# MiniPrinterController.net
KiCad netlist of a schematic drawn in EAGLE
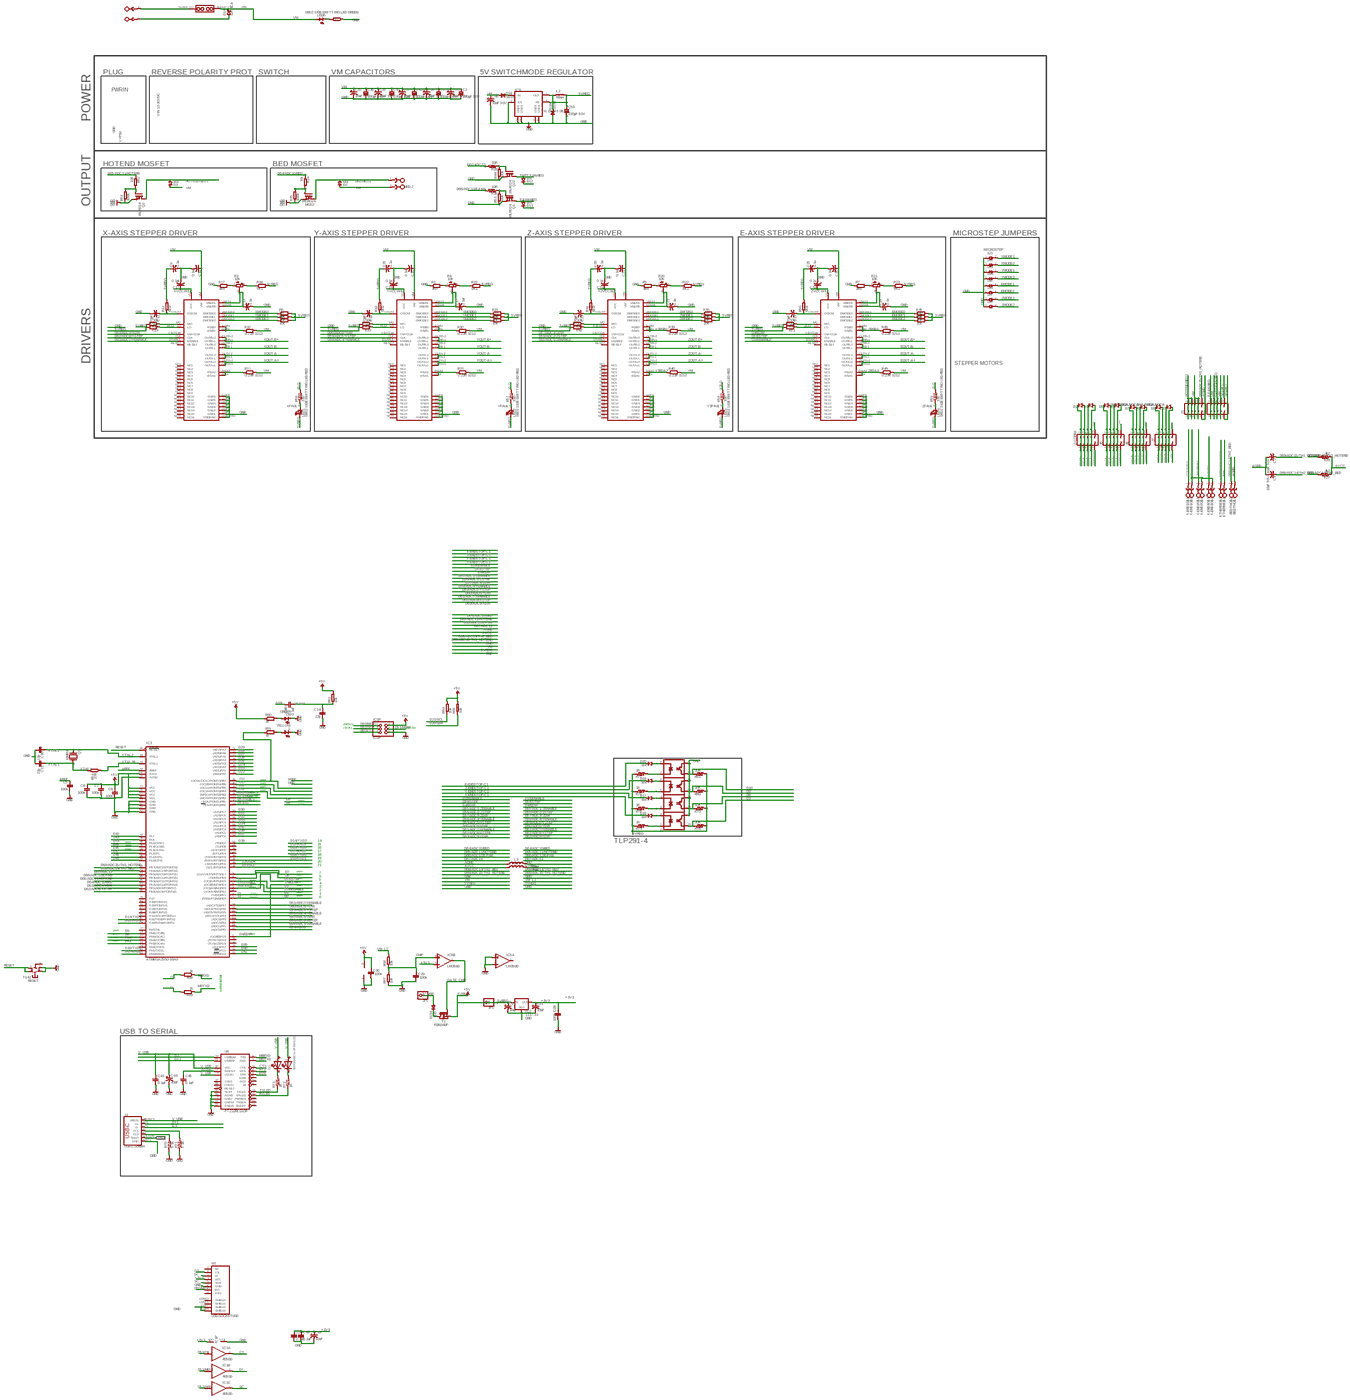
[diagram p0: schematic, sheet 1, overview]
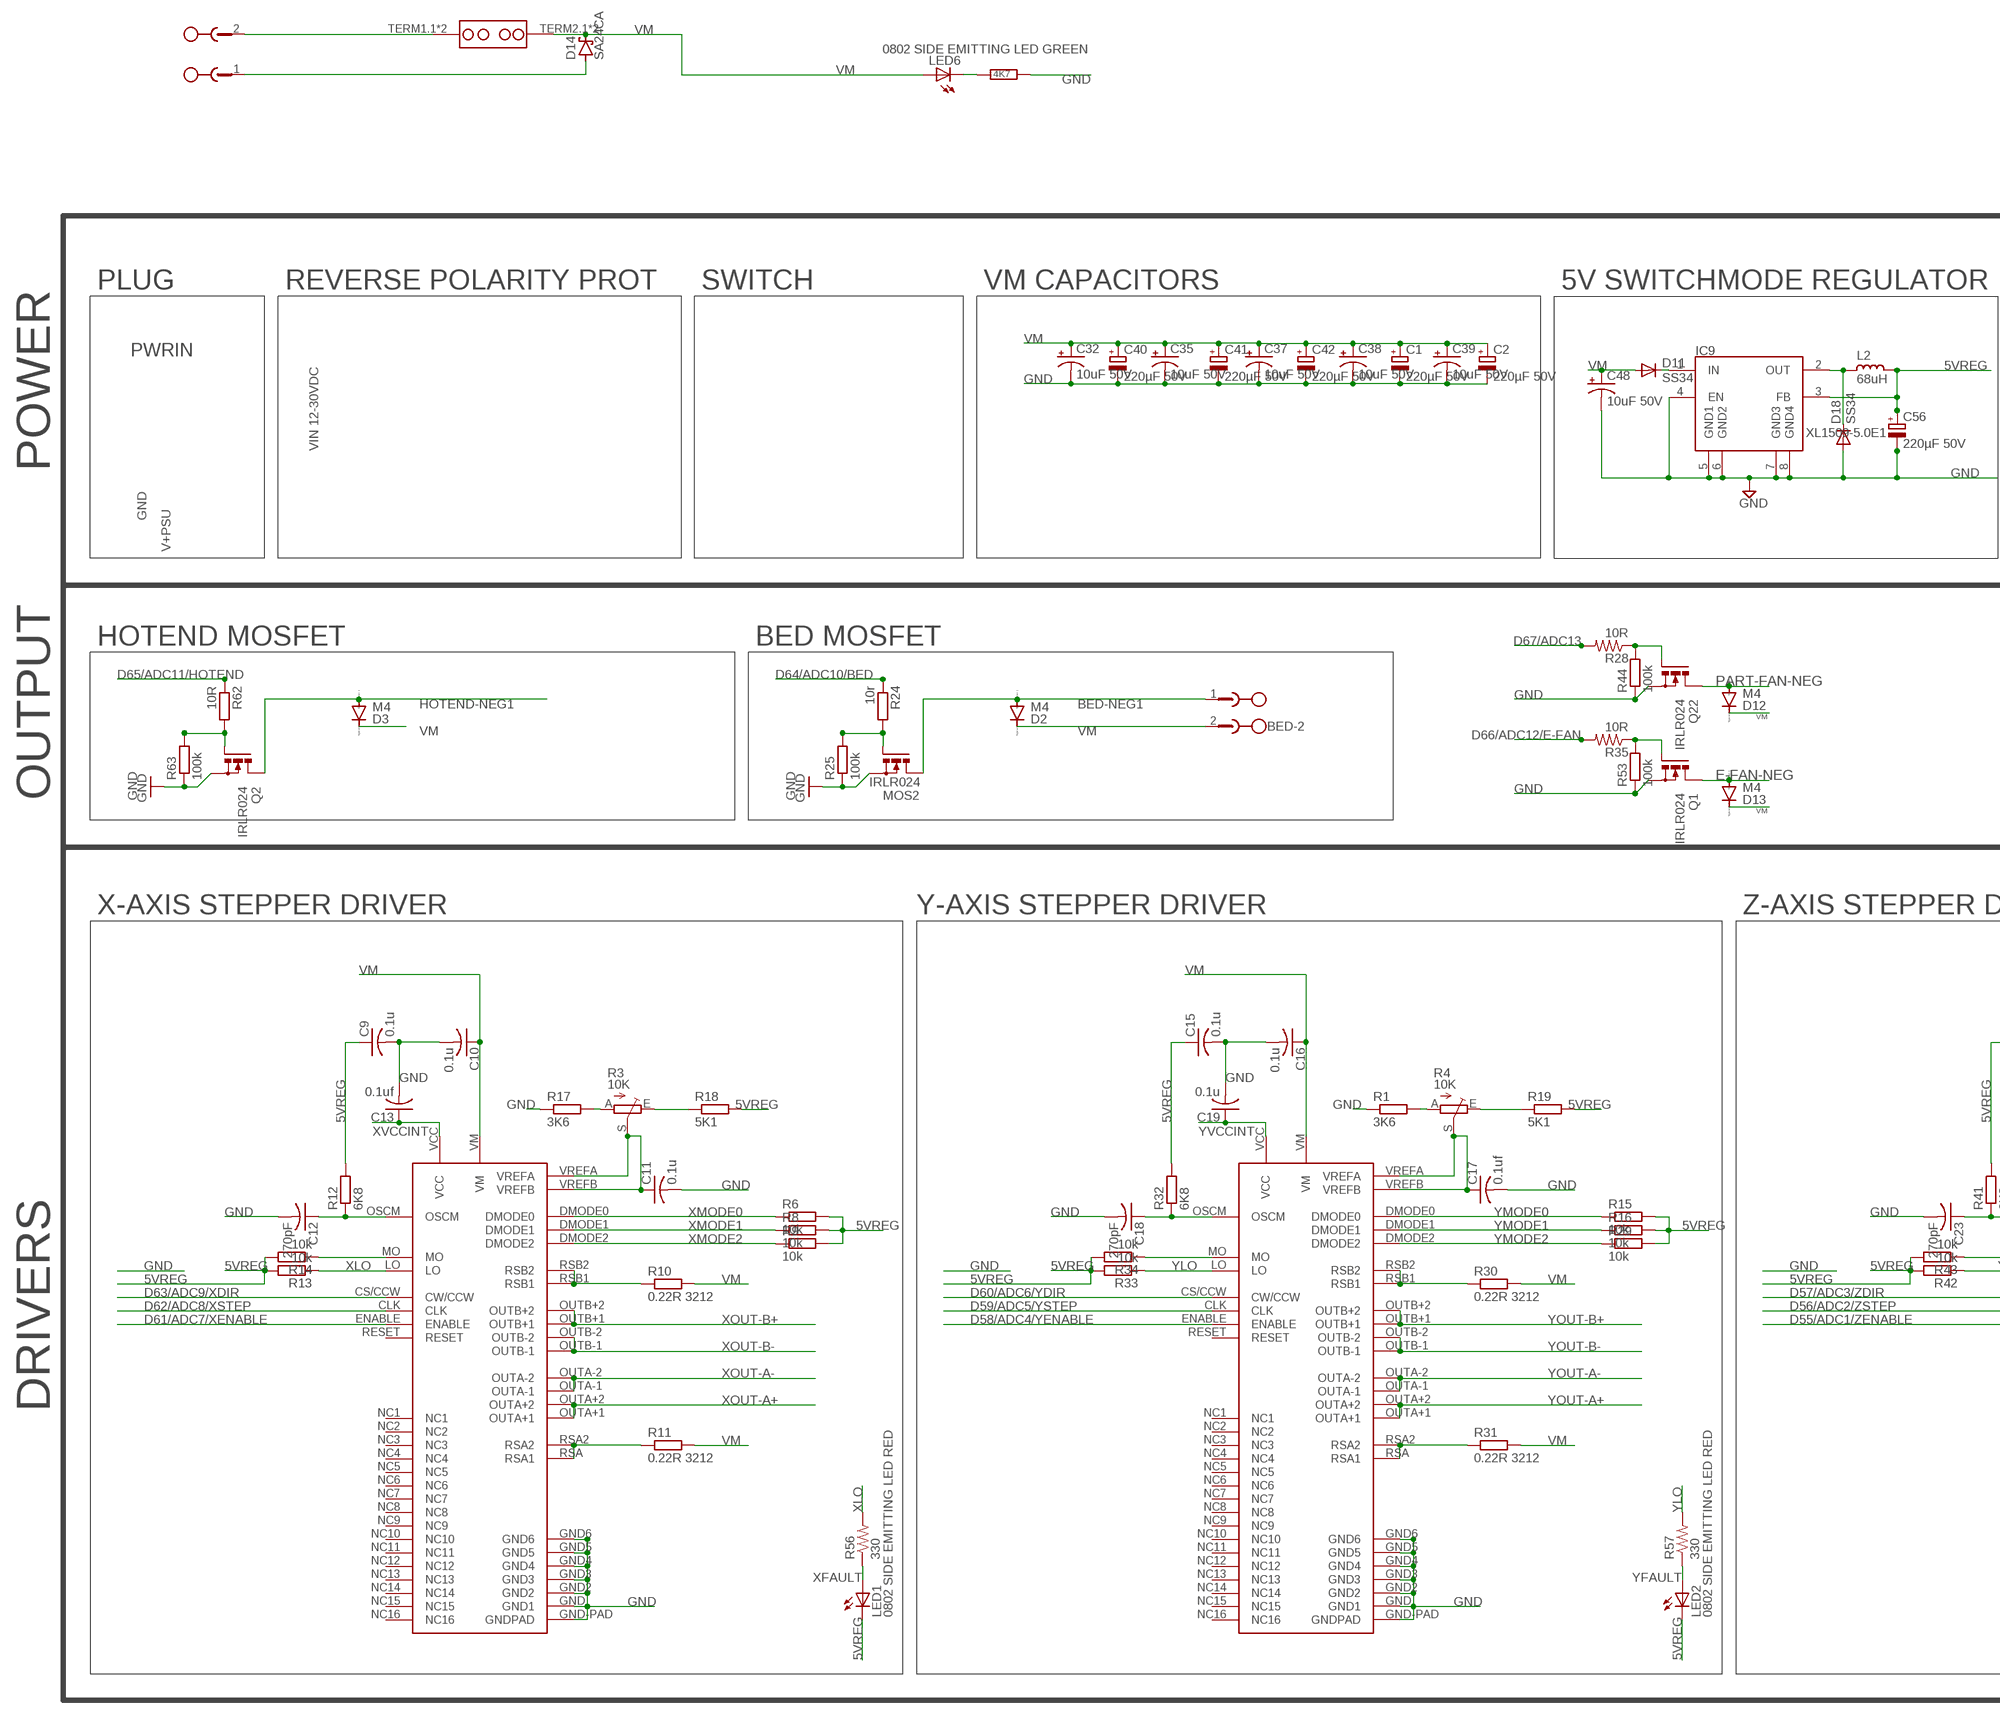
[diagram p1: schematic, sheet 1, part 1 of 7]
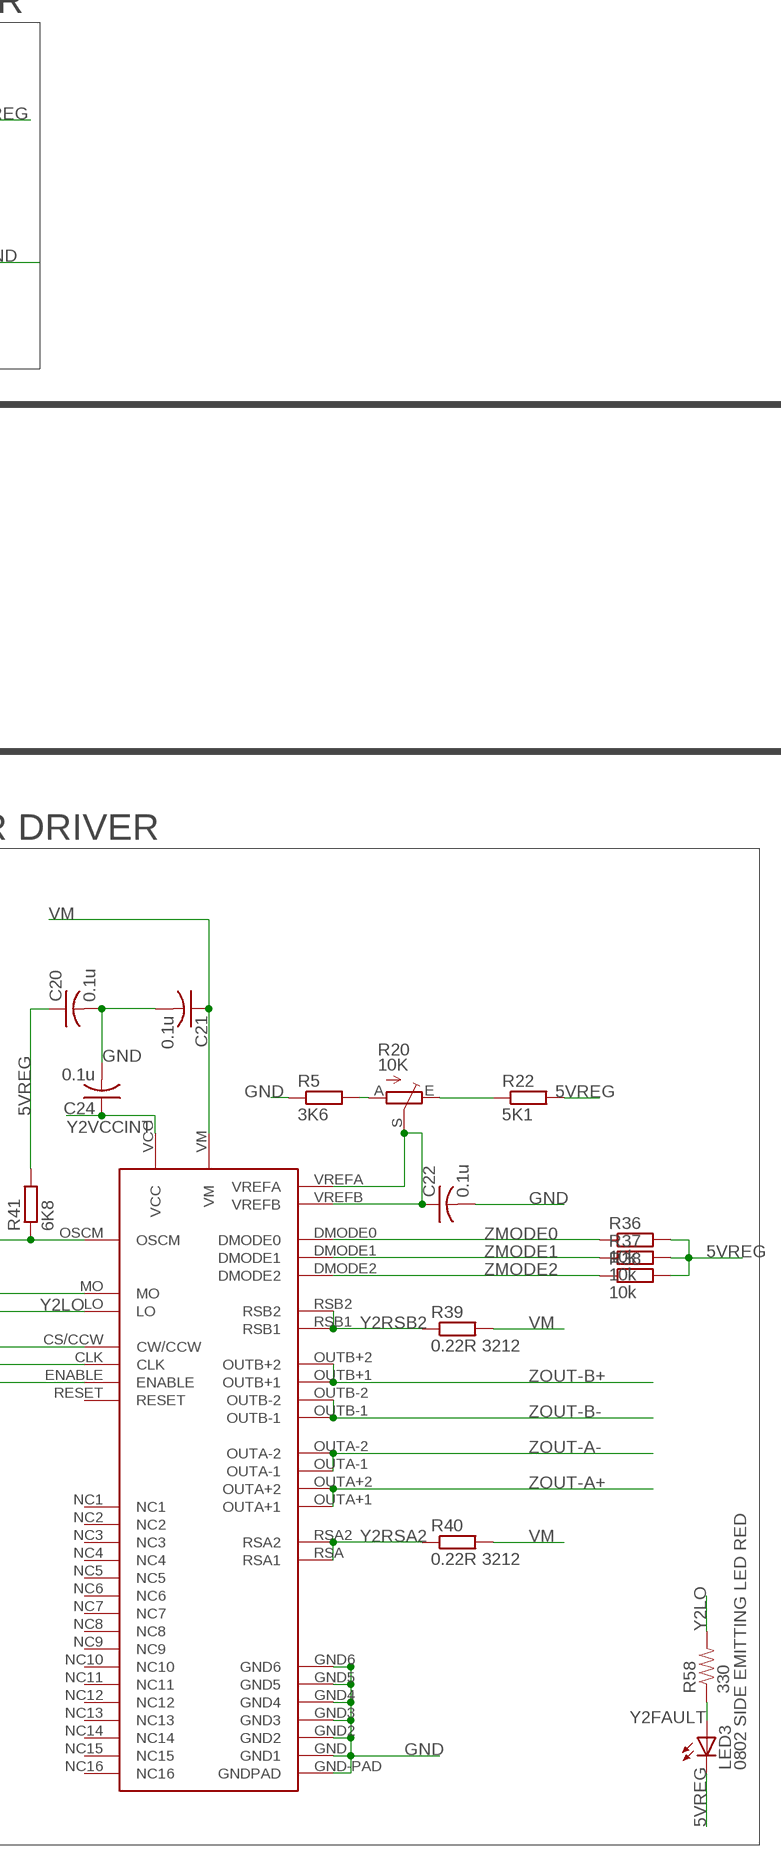
[diagram p2: schematic, sheet 1, part 2 of 7]
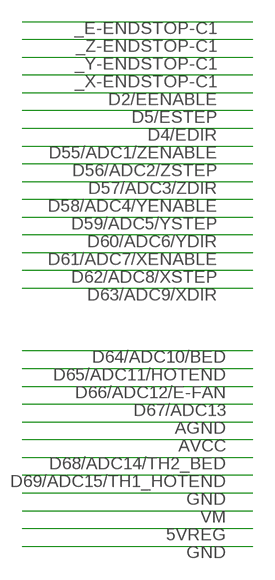
[diagram p3: schematic, sheet 1, part 3 of 7]
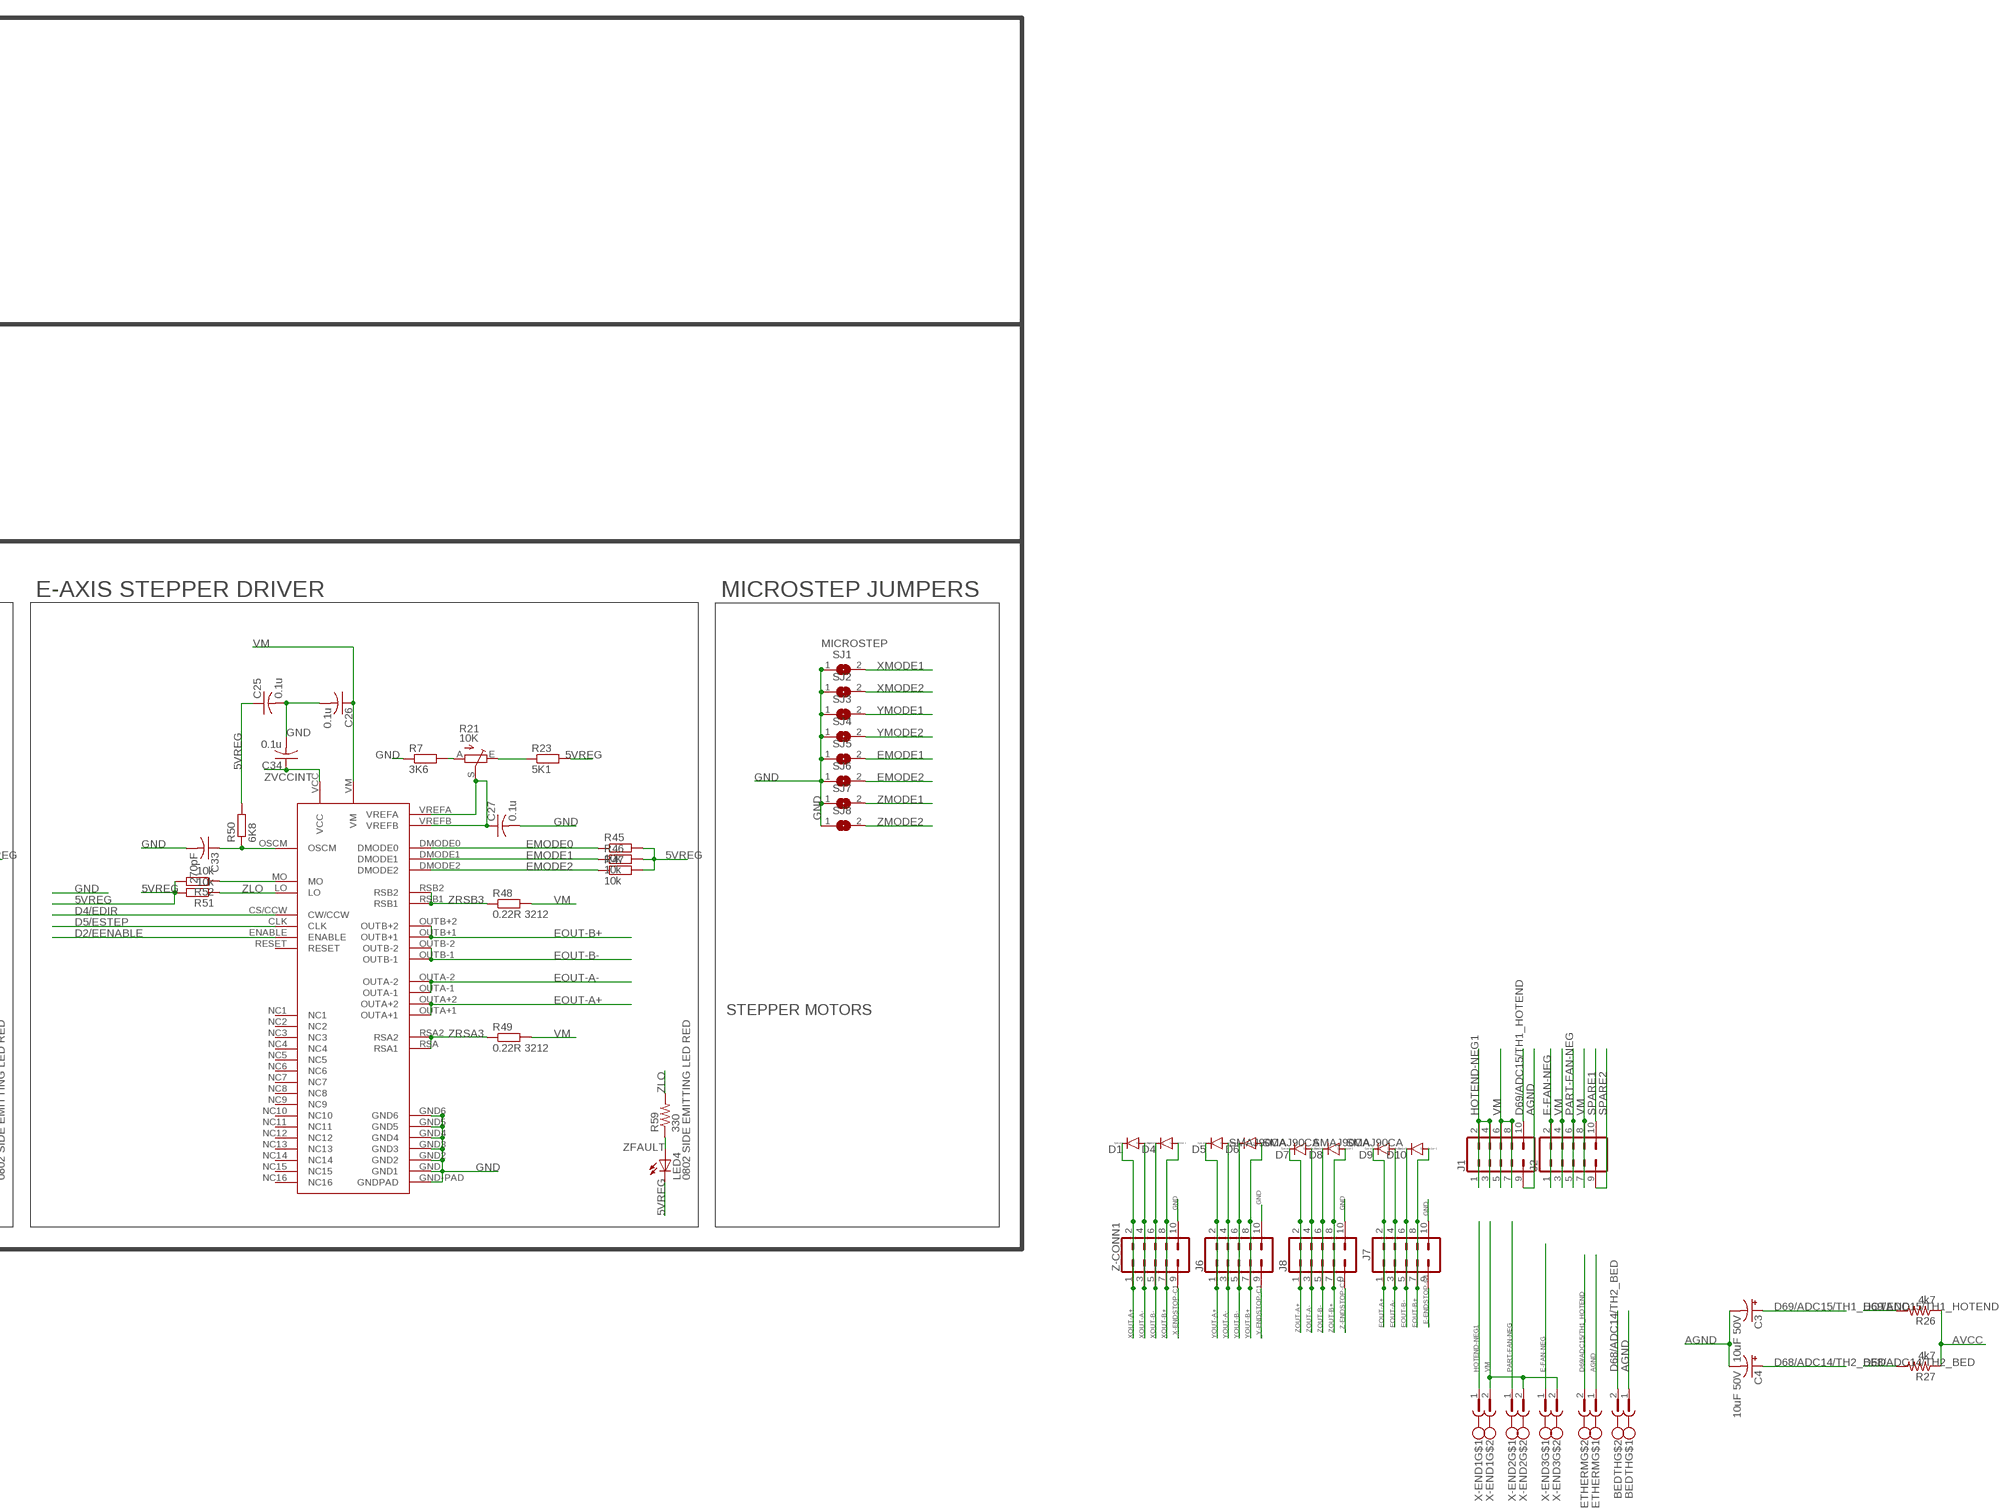
[diagram p4: schematic, sheet 1, part 4 of 7]
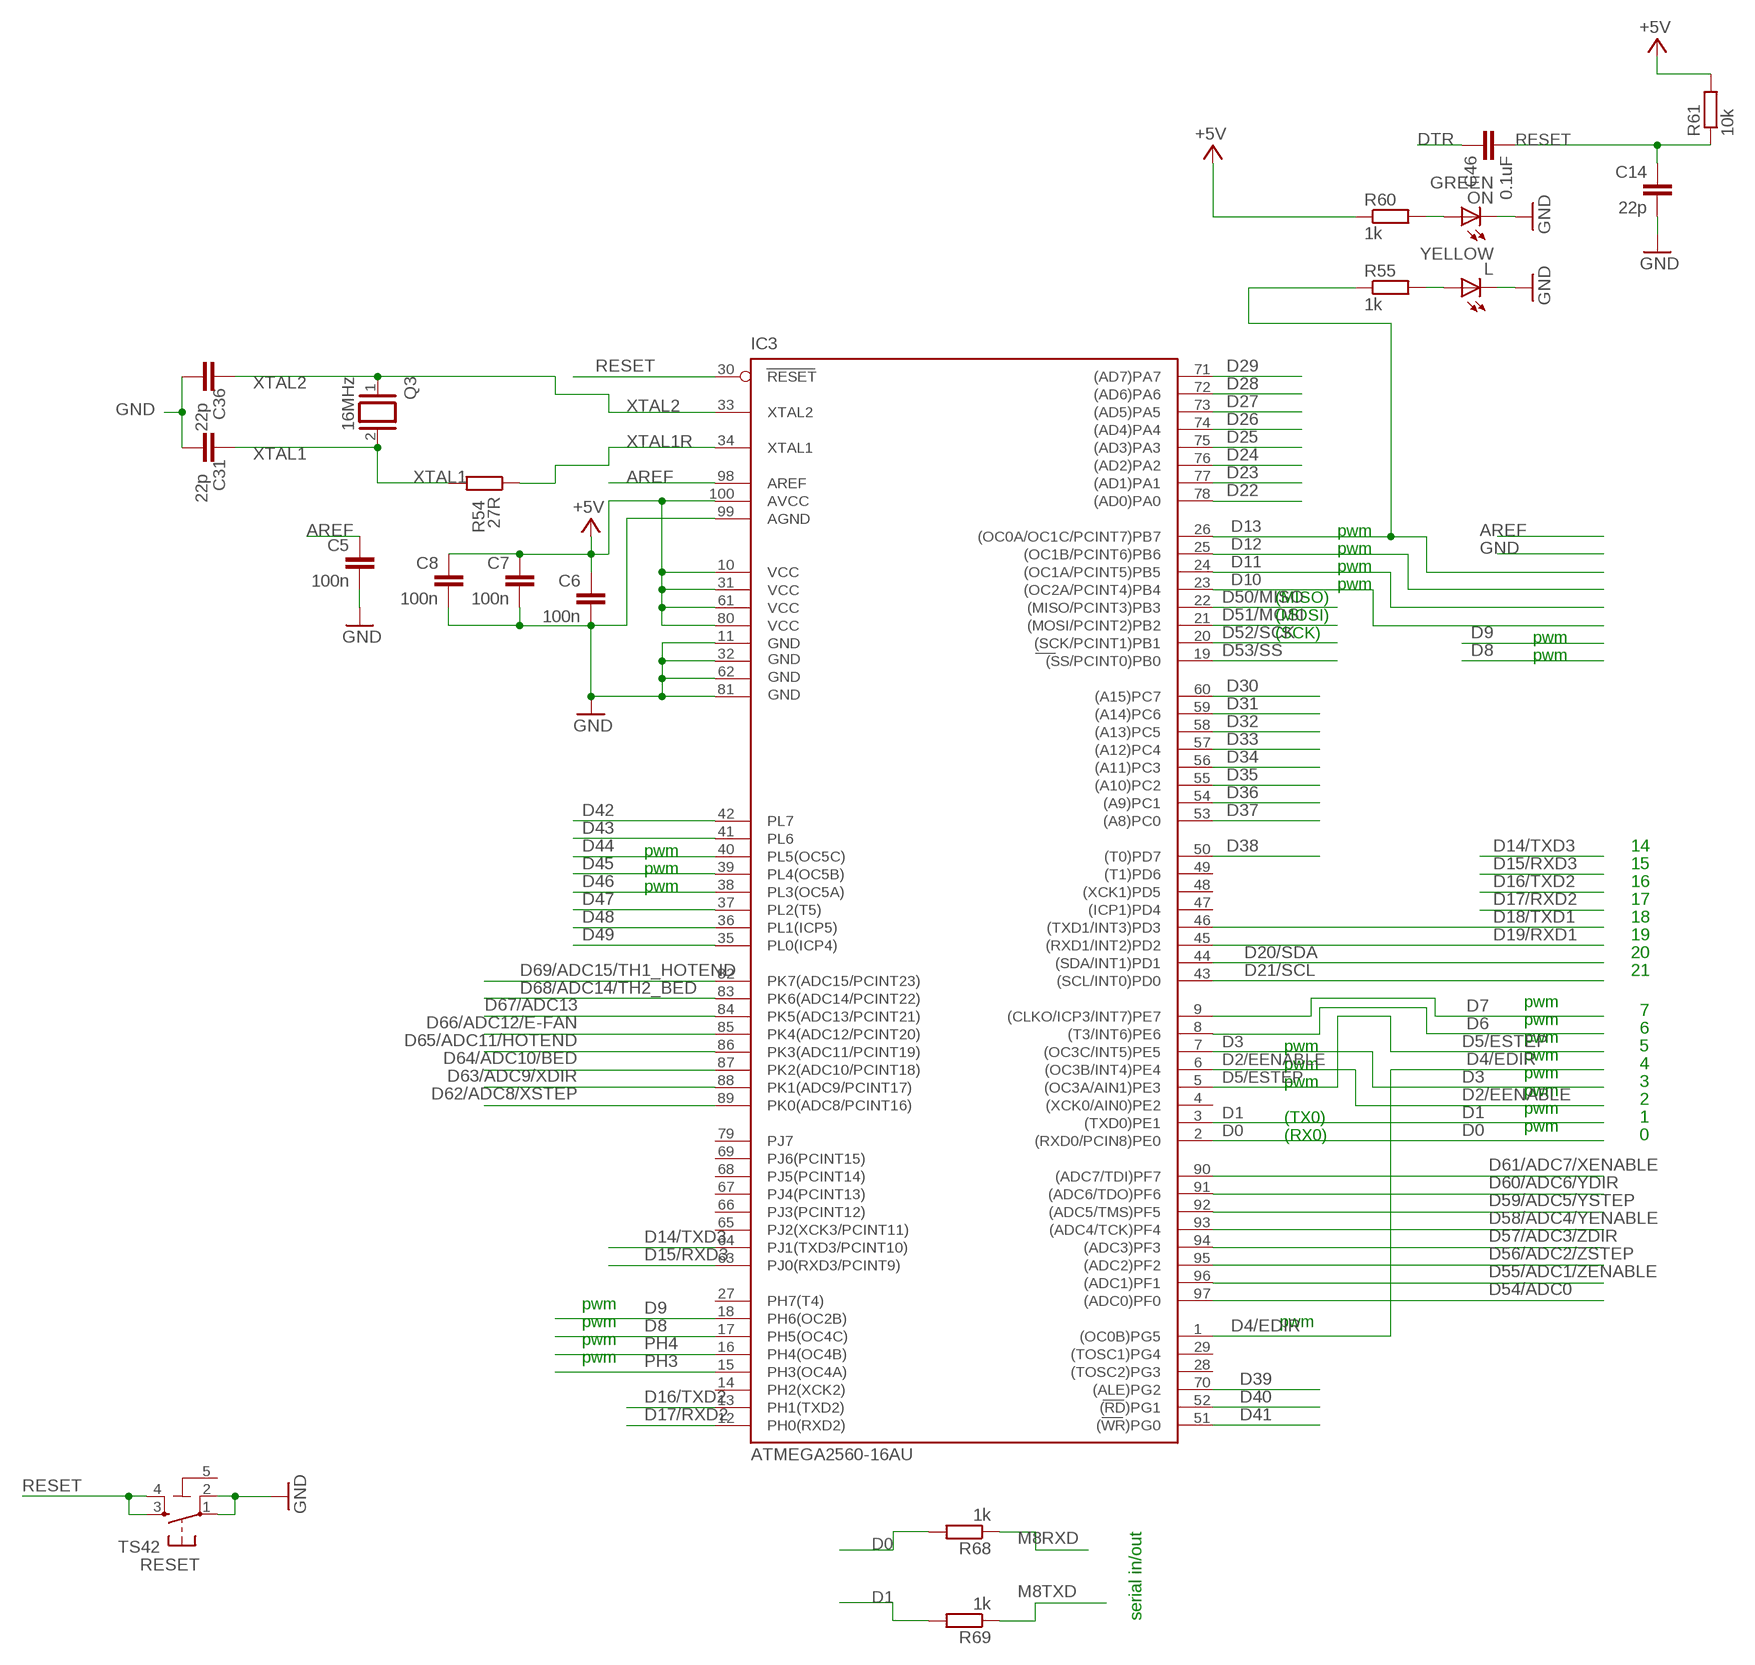
[diagram p5: schematic, sheet 1, part 5 of 7]
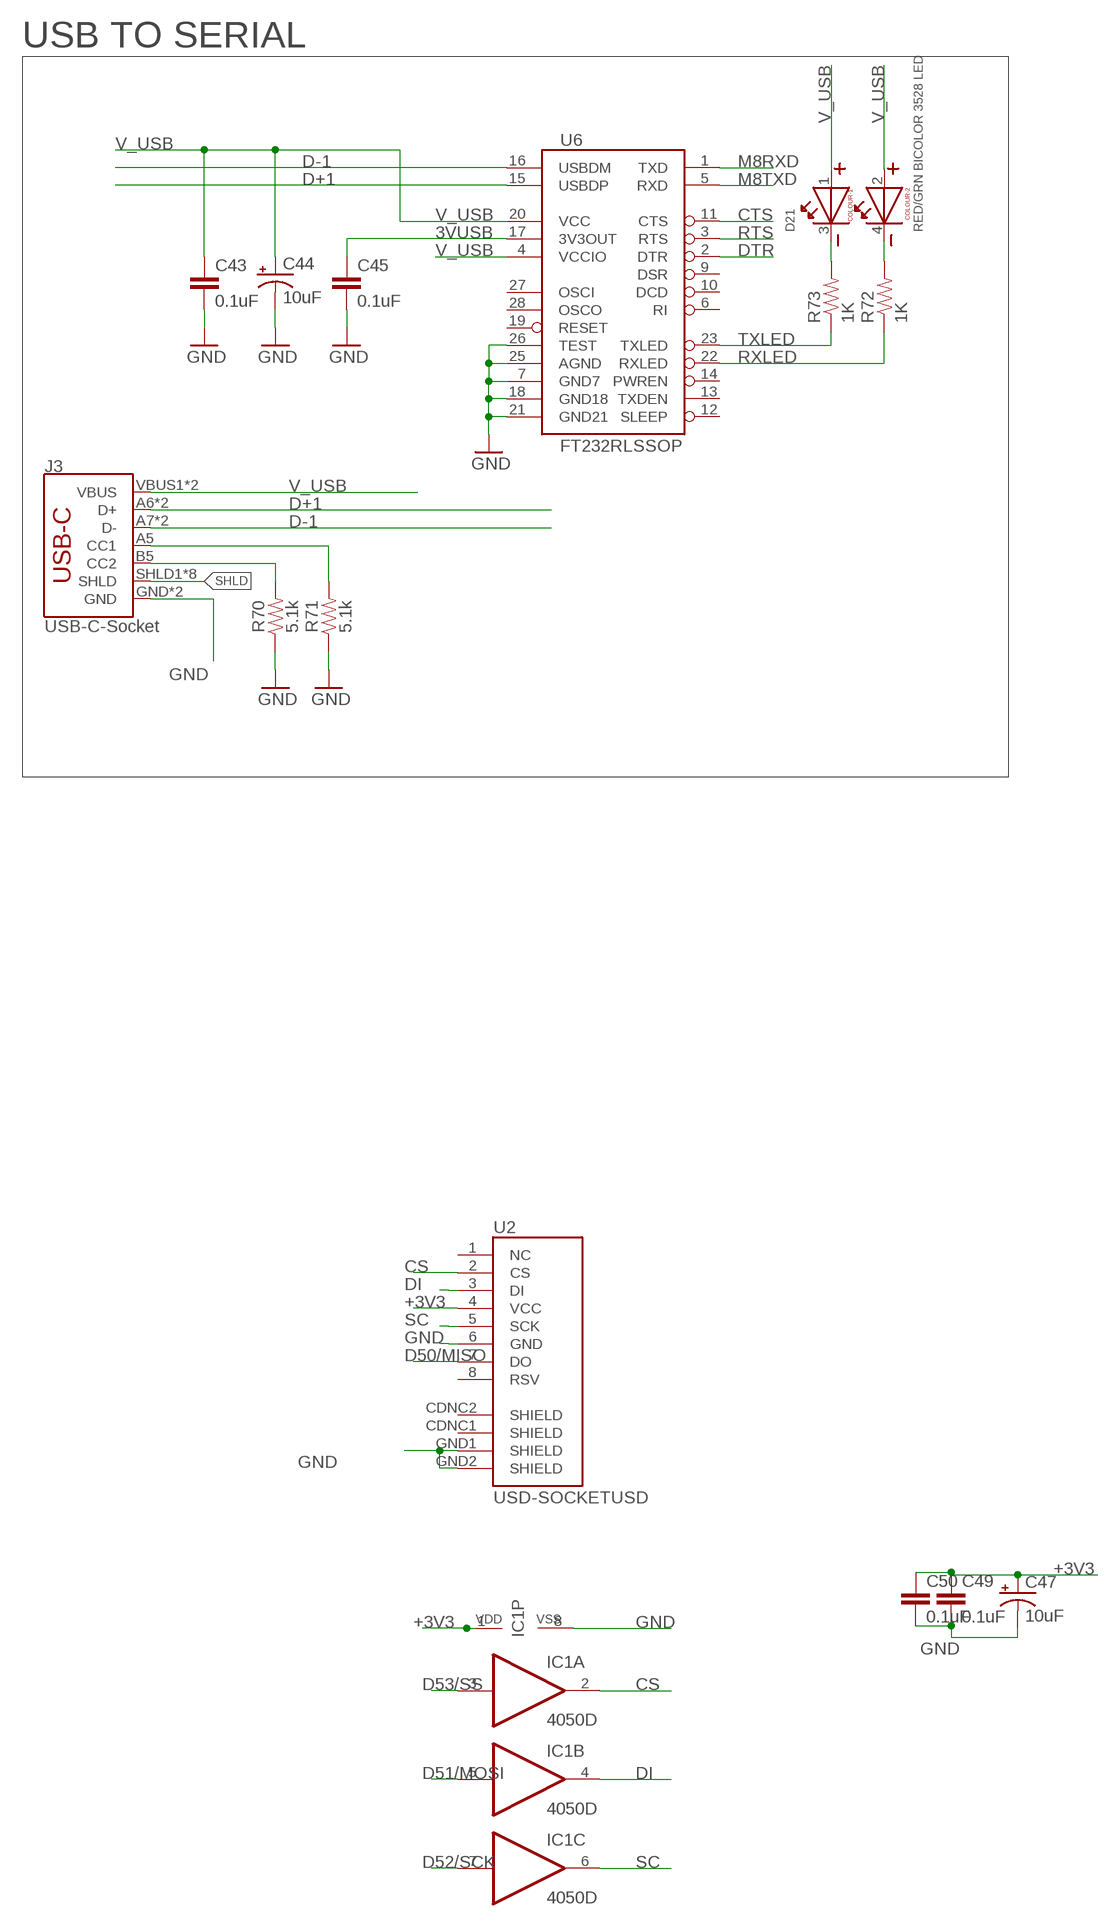
[diagram p6: schematic, sheet 1, part 6 of 7]
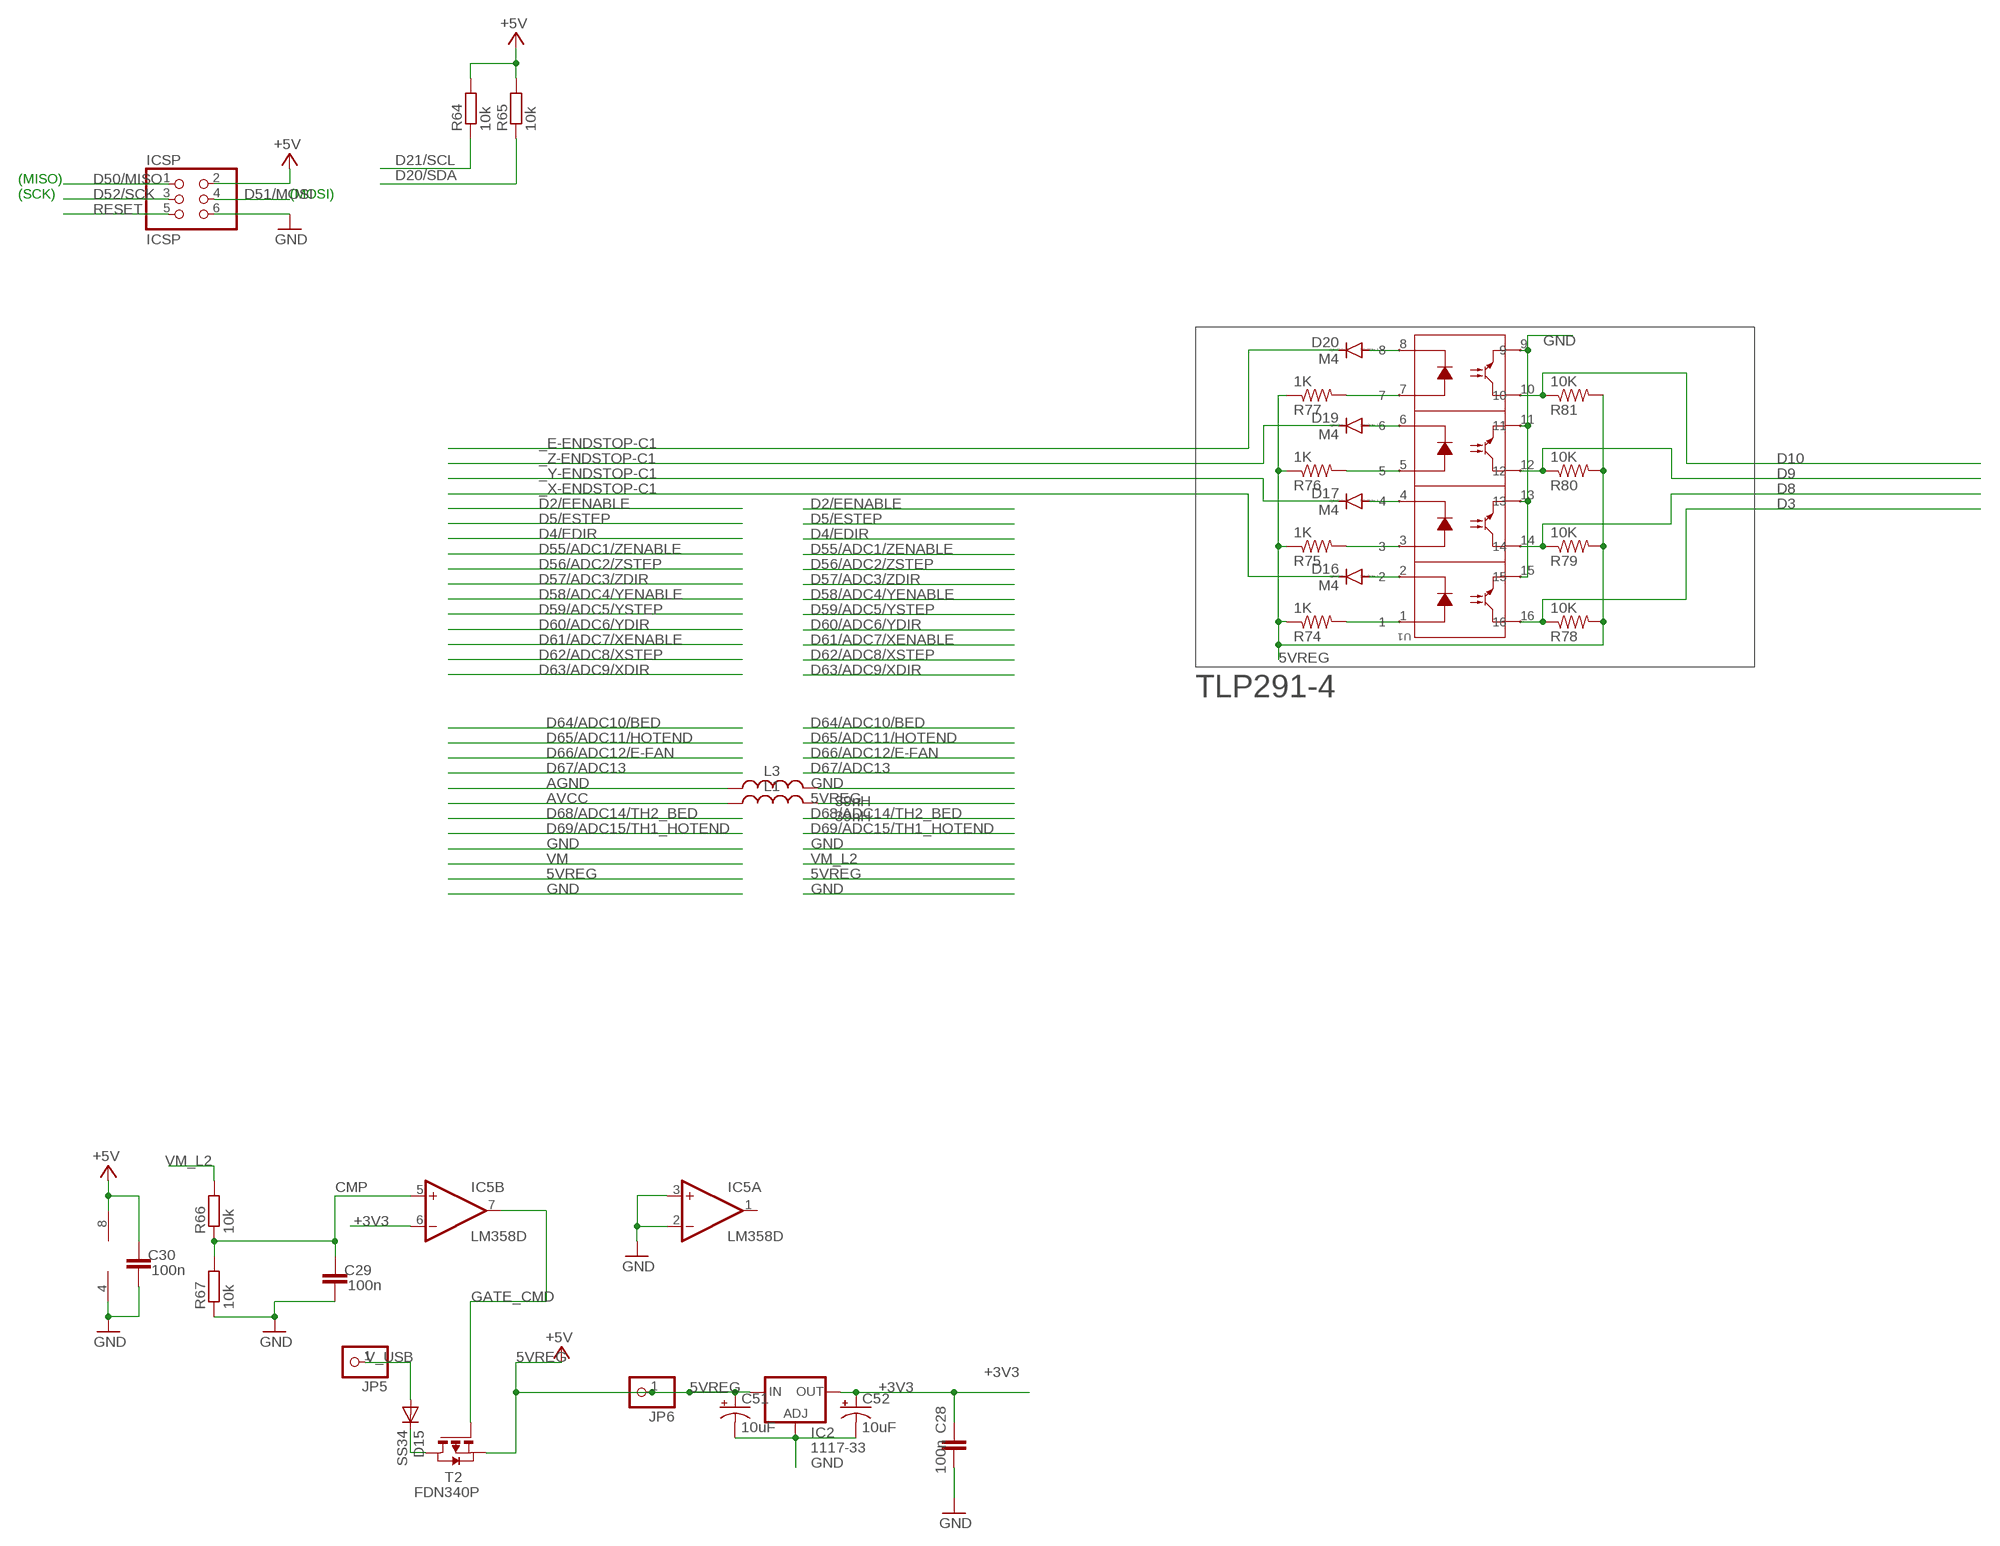
[diagram p7: schematic, sheet 1, part 7 of 7]

(export (version "E")
  (design (tool "Eeschema 10.0.6"))
  (components
    (comp (ref "BED")
      (value "Phoenix Pluggable 5.08mm 2 way")
      (footprint "eagle-import:MSTBA2")
      (fields (field (name "MF") "FARNELL") (field (name "MPN") "1757242"))
      (libsource (lib "eagle-import") (part "MSTBA2"))
    )
    (comp (ref "BEDTH")
      (value "Phoenix Pluggable 3.81mm 2 way")
      (footprint "eagle-import:MC1.5_2-G-3.81")
      (libsource (lib "eagle-import") (part "MC1.5/2"))
    )
    (comp (ref "C1")
      (value "220µF 50V")
      (footprint "eagle-import:E3,5-10")
      (libsource (lib "eagle-import") (part "CPOL-EUE3.5-10"))
    )
    (comp (ref "C2")
      (value "220µF 50V")
      (footprint "eagle-import:E3,5-10")
      (libsource (lib "eagle-import") (part "CPOL-EUE3.5-10"))
    )
    (comp (ref "C3")
      (value "10uF 50V")
      (footprint "eagle-import:EIA3216")
      (libsource (lib "eagle-import") (part "CAP_POL1206"))
    )
    (comp (ref "C4")
      (value "10uF 50V")
      (footprint "eagle-import:EIA3216")
      (libsource (lib "eagle-import") (part "CAP_POL1206"))
    )
    (comp (ref "C5")
      (value "100n")
      (footprint "eagle-import:C0603-ROUND")
      (libsource (lib "eagle-import") (part "C-EU0603-RND"))
    )
    (comp (ref "C6")
      (value "100n")
      (footprint "eagle-import:C0603-ROUND")
      (libsource (lib "eagle-import") (part "C-EU0603-RND"))
    )
    (comp (ref "C7")
      (value "100n")
      (footprint "eagle-import:C0603-ROUND")
      (libsource (lib "eagle-import") (part "C-EU0603-RND"))
    )
    (comp (ref "C8")
      (value "100n")
      (footprint "eagle-import:C0603-ROUND")
      (libsource (lib "eagle-import") (part "C-EU0603-RND"))
    )
    (comp (ref "C9")
      (value "0.1u")
      (footprint "eagle-import:C0603K")
      (libsource (lib "eagle-import") (part "C-USC0603K"))
    )
    (comp (ref "C10")
      (value "0.1u")
      (footprint "eagle-import:C0603K")
      (libsource (lib "eagle-import") (part "C-USC0603K"))
    )
    (comp (ref "C11")
      (value "0.1u")
      (footprint "eagle-import:C0603K")
      (libsource (lib "eagle-import") (part "C-USC0603K"))
    )
    (comp (ref "C12")
      (value "270pF")
      (footprint "eagle-import:C0603K")
      (libsource (lib "eagle-import") (part "C-USC0603K"))
    )
    (comp (ref "C13")
      (value "0.1uf")
      (footprint "eagle-import:C0603K")
      (libsource (lib "eagle-import") (part "C-USC0603K"))
    )
    (comp (ref "C14")
      (value "22p")
      (footprint "eagle-import:C0603-ROUND")
      (libsource (lib "eagle-import") (part "C-EU0603-RND"))
    )
    (comp (ref "C15")
      (value "0.1u")
      (footprint "eagle-import:C0603K")
      (libsource (lib "eagle-import") (part "C-USC0603K"))
    )
    (comp (ref "C16")
      (value "0.1u")
      (footprint "eagle-import:C0603K")
      (libsource (lib "eagle-import") (part "C-USC0603K"))
    )
    (comp (ref "C17")
      (value "0.1uf")
      (footprint "eagle-import:C0603K")
      (libsource (lib "eagle-import") (part "C-USC0603K"))
    )
    (comp (ref "C18")
      (value "270pF")
      (footprint "eagle-import:C0603K")
      (libsource (lib "eagle-import") (part "C-USC0603K"))
    )
    (comp (ref "C19")
      (value "0.1u")
      (footprint "eagle-import:C0603K")
      (libsource (lib "eagle-import") (part "C-USC0603K"))
    )
    (comp (ref "C20")
      (value "0.1u")
      (footprint "eagle-import:C0603K")
      (libsource (lib "eagle-import") (part "C-USC0603K"))
    )
    (comp (ref "C21")
      (value "0.1u")
      (footprint "eagle-import:C0603K")
      (libsource (lib "eagle-import") (part "C-USC0603K"))
    )
    (comp (ref "C22")
      (value "0.1u")
      (footprint "eagle-import:C0603K")
      (libsource (lib "eagle-import") (part "C-USC0603K"))
    )
    (comp (ref "C23")
      (value "270pF")
      (footprint "eagle-import:C0603K")
      (libsource (lib "eagle-import") (part "C-USC0603K"))
    )
    (comp (ref "C24")
      (value "0.1u")
      (footprint "eagle-import:C0603K")
      (libsource (lib "eagle-import") (part "C-USC0603K"))
    )
    (comp (ref "C25")
      (value "0.1u")
      (footprint "eagle-import:C0603K")
      (libsource (lib "eagle-import") (part "C-USC0603K"))
    )
    (comp (ref "C26")
      (value "0.1u")
      (footprint "eagle-import:C0603K")
      (libsource (lib "eagle-import") (part "C-USC0603K"))
    )
    (comp (ref "C27")
      (value "0.1u")
      (footprint "eagle-import:C0603K")
      (libsource (lib "eagle-import") (part "C-USC0603K"))
    )
    (comp (ref "C28")
      (value "100n")
      (footprint "eagle-import:C0603-ROUND")
      (libsource (lib "eagle-import") (part "C-EU0603-RND"))
    )
    (comp (ref "C29")
      (value "100n")
      (footprint "eagle-import:C0603-ROUND")
      (libsource (lib "eagle-import") (part "C-EU0603-RND"))
    )
    (comp (ref "C30")
      (value "100n")
      (footprint "eagle-import:C0603")
      (libsource (lib "eagle-import") (part "rcl_C-EUC0603"))
    )
    (comp (ref "C31")
      (value "22p")
      (footprint "eagle-import:C0603-ROUND")
      (libsource (lib "eagle-import") (part "C-EU0603-RND"))
    )
    (comp (ref "C32")
      (value "10uF 50V")
      (footprint "eagle-import:EIA3216")
      (libsource (lib "eagle-import") (part "CAP_POL1206"))
    )
    (comp (ref "C33")
      (value "270pF")
      (footprint "eagle-import:C0603K")
      (libsource (lib "eagle-import") (part "C-USC0603K"))
    )
    (comp (ref "C34")
      (value "0.1u")
      (footprint "eagle-import:C0603K")
      (libsource (lib "eagle-import") (part "C-USC0603K"))
    )
    (comp (ref "C35")
      (value "10uF 50V")
      (footprint "eagle-import:EIA3216")
      (libsource (lib "eagle-import") (part "CAP_POL1206"))
    )
    (comp (ref "C36")
      (value "22p")
      (footprint "eagle-import:C0603-ROUND")
      (libsource (lib "eagle-import") (part "C-EU0603-RND"))
    )
    (comp (ref "C37")
      (value "10uF 50V")
      (footprint "eagle-import:EIA3216")
      (libsource (lib "eagle-import") (part "CAP_POL1206"))
    )
    (comp (ref "C38")
      (value "10uF 50V")
      (footprint "eagle-import:EIA3216")
      (libsource (lib "eagle-import") (part "CAP_POL1206"))
    )
    (comp (ref "C39")
      (value "10uF 50V")
      (footprint "eagle-import:EIA3216")
      (libsource (lib "eagle-import") (part "CAP_POL1206"))
    )
    (comp (ref "C40")
      (value "220µF 50V")
      (footprint "eagle-import:E3,5-10")
      (libsource (lib "eagle-import") (part "CPOL-EUE3.5-10"))
    )
    (comp (ref "C41")
      (value "220µF 50V")
      (footprint "eagle-import:E3,5-10")
      (libsource (lib "eagle-import") (part "CPOL-EUE3.5-10"))
    )
    (comp (ref "C42")
      (value "220µF 50V")
      (footprint "eagle-import:E3,5-10")
      (libsource (lib "eagle-import") (part "CPOL-EUE3.5-10"))
    )
    (comp (ref "C43")
      (value "0.1uF")
      (footprint "eagle-import:0603-CAP")
      (libsource (lib "eagle-import") (part "CAP0603-CAP"))
    )
    (comp (ref "C44")
      (value "10uF")
      (footprint "eagle-import:EIA3216")
      (libsource (lib "eagle-import") (part "CAP_POL1206"))
    )
    (comp (ref "C45")
      (value "0.1uF")
      (footprint "eagle-import:0603-CAP")
      (libsource (lib "eagle-import") (part "CAP0603-CAP"))
    )
    (comp (ref "C46")
      (value "0.1uF")
      (footprint "eagle-import:C0603-ROUND")
      (libsource (lib "eagle-import") (part "C-EU0603-RND"))
    )
    (comp (ref "C47")
      (value "10uF")
      (footprint "eagle-import:EIA3216")
      (libsource (lib "eagle-import") (part "CAP_POL1206"))
    )
    (comp (ref "C48")
      (value "10uF 50V")
      (footprint "eagle-import:EIA3216")
      (libsource (lib "eagle-import") (part "CAP_POL1206"))
    )
    (comp (ref "C49")
      (value "0.1uF")
      (footprint "eagle-import:0603-CAP")
      (libsource (lib "eagle-import") (part "CAP0603-CAP"))
    )
    (comp (ref "C50")
      (value "0.1uF")
      (footprint "eagle-import:0603-CAP")
      (libsource (lib "eagle-import") (part "CAP0603-CAP"))
    )
    (comp (ref "C51")
      (value "10uF")
      (footprint "eagle-import:EIA3216")
      (libsource (lib "eagle-import") (part "CAP_POL1206"))
    )
    (comp (ref "C52")
      (value "10uF")
      (footprint "eagle-import:EIA3216")
      (libsource (lib "eagle-import") (part "CAP_POL1206"))
    )
    (comp (ref "C56")
      (value "220µF 50V")
      (footprint "eagle-import:E3,5-10")
      (libsource (lib "eagle-import") (part "CPOL-EUE3.5-10"))
    )
    (comp (ref "D1")
      (value "SMAJ90CA")
      (footprint "eagle-import:DO-214AC")
      (libsource (lib "eagle-import") (part "DIODE-DO-214AC"))
    )
    (comp (ref "D2")
      (value "M4")
      (footprint "eagle-import:DO-214AC")
      (libsource (lib "eagle-import") (part "DIODE-DO-214AC"))
    )
    (comp (ref "D3")
      (value "M4")
      (footprint "eagle-import:DO-214AC")
      (libsource (lib "eagle-import") (part "DIODE-DO-214AC"))
    )
    (comp (ref "D4")
      (value "SMAJ90CA")
      (footprint "eagle-import:DO-214AC")
      (libsource (lib "eagle-import") (part "DIODE-DO-214AC"))
    )
    (comp (ref "D5")
      (value "SMAJ90CA")
      (footprint "eagle-import:DO-214AC")
      (libsource (lib "eagle-import") (part "DIODE-DO-214AC"))
    )
    (comp (ref "D6")
      (value "SMAJ90CA")
      (footprint "eagle-import:DO-214AC")
      (libsource (lib "eagle-import") (part "DIODE-DO-214AC"))
    )
    (comp (ref "D7")
      (value "SMAJ90CA")
      (footprint "eagle-import:DO-214AC")
      (libsource (lib "eagle-import") (part "DIODE-DO-214AC"))
    )
    (comp (ref "D8")
      (value "SMAJ90CA")
      (footprint "eagle-import:DO-214AC")
      (libsource (lib "eagle-import") (part "DIODE-DO-214AC"))
    )
    (comp (ref "D9")
      (value "SMAJ90CA")
      (footprint "eagle-import:DO-214AC")
      (libsource (lib "eagle-import") (part "DIODE-DO-214AC"))
    )
    (comp (ref "D10")
      (value "SMAJ90CA")
      (footprint "eagle-import:DO-214AC")
      (libsource (lib "eagle-import") (part "DIODE-DO-214AC"))
    )
    (comp (ref "D11")
      (value "SS34")
      (footprint "eagle-import:DO-214AC")
      (libsource (lib "eagle-import") (part "dp_devices_DIODE-DO-214AC"))
    )
    (comp (ref "D12")
      (value "M4")
      (footprint "eagle-import:DO-214AC")
      (libsource (lib "eagle-import") (part "DIODE-DO-214AC"))
    )
    (comp (ref "D13")
      (value "M4")
      (footprint "eagle-import:DO-214AC")
      (libsource (lib "eagle-import") (part "DIODE-DO-214AC"))
    )
    (comp (ref "D14")
      (value "SA24CA")
      (footprint "eagle-import:C4111-15")
      (libsource (lib "eagle-import") (part "1N6267A"))
    )
    (comp (ref "D15")
      (value "SS34")
      (footprint "eagle-import:DO-214AC")
      (libsource (lib "eagle-import") (part "dp_devices_DIODE-DO-214AC"))
    )
    (comp (ref "D16")
      (value "M4")
      (footprint "eagle-import:DO-214AC")
      (libsource (lib "eagle-import") (part "DIODE-DO-214AC"))
    )
    (comp (ref "D17")
      (value "M4")
      (footprint "eagle-import:DO-214AC")
      (libsource (lib "eagle-import") (part "DIODE-DO-214AC"))
    )
    (comp (ref "D18")
      (value "SS34")
      (footprint "eagle-import:DO-214AC")
      (libsource (lib "eagle-import") (part "dp_devices_DIODE-DO-214AC"))
    )
    (comp (ref "D19")
      (value "M4")
      (footprint "eagle-import:DO-214AC")
      (libsource (lib "eagle-import") (part "DIODE-DO-214AC"))
    )
    (comp (ref "D20")
      (value "M4")
      (footprint "eagle-import:DO-214AC")
      (libsource (lib "eagle-import") (part "DIODE-DO-214AC"))
    )
    (comp (ref "D21")
      (value "RED/GRN BICOLOR 3528 LED")
      (footprint "eagle-import:3528")
      (fields
        (field (name "MANUFACTURER") "Würth Elektronik eiSos GmbH")
        (field (name "CREATED-BY") "Christin Otto")
      )
      (libsource (lib "eagle-import") (part "WL-SBTW-150141RB73100-R&B"))
    )
    (comp (ref "ETHERM")
      (value "Phoenix Pluggable 3.81mm 2 way")
      (footprint "eagle-import:MC1.5_2-G-3.81")
      (libsource (lib "eagle-import") (part "MC1.5/2"))
    )
    (comp (ref "IC1")
      (value "4050D")
      (footprint "eagle-import:SO16")
      (libsource (lib "eagle-import") (part "4050D"))
    )
    (comp (ref "IC2")
      (value "1117-33")
      (footprint "eagle-import:SOT223")
      (libsource (lib "eagle-import") (part "LD117A?S33TR"))
    )
    (comp (ref "IC3")
      (value "ATMEGA2560-16AU")
      (footprint "eagle-import:TQFP100")
      (libsource (lib "eagle-import") (part "ATMEGAAU1280-16"))
    )
    (comp (ref "IC5")
      (value "LM358D")
      (footprint "eagle-import:SO08")
      (libsource (lib "eagle-import") (part "LM358D"))
    )
    (comp (ref "IC9")
      (value "XL1509-5.0E1")
      (footprint "eagle-import:SO08")
      (libsource (lib "eagle-import") (part "XL1509"))
    )
    (comp (ref "ICSP")
      (value "ICSP")
      (footprint "eagle-import:2X03")
      (libsource (lib "eagle-import") (part "PINHD-2X3"))
    )
    (comp (ref "J1")
      (value "CONN_05X2SHD_LOCK")
      (footprint "eagle-import:2X5-SHROUDED_LOCK")
      (libsource (lib "eagle-import") (part "CONN_05X2SHD_LOCK"))
    )
    (comp (ref "J2")
      (value "CONN_05X2SHD_LOCK")
      (footprint "eagle-import:2X5-SHROUDED_LOCK")
      (libsource (lib "eagle-import") (part "CONN_05X2SHD_LOCK"))
    )
    (comp (ref "J3")
      (value "USB-C-Socket")
      (footprint "eagle-import:USB-C-16P")
      (libsource (lib "eagle-import") (part "USB_C16PIN"))
    )
    (comp (ref "J6")
      (value "CONN_05X2SHD_LOCK")
      (footprint "eagle-import:2X5-SHROUDED_LOCK")
      (libsource (lib "eagle-import") (part "CONN_05X2SHD_LOCK"))
    )
    (comp (ref "J7")
      (value "CONN_05X2SHD_LOCK")
      (footprint "eagle-import:2X5-SHROUDED_LOCK")
      (libsource (lib "eagle-import") (part "CONN_05X2SHD_LOCK"))
    )
    (comp (ref "J8")
      (value "CONN_05X2SHD_LOCK")
      (footprint "eagle-import:2X5-SHROUDED_LOCK")
      (libsource (lib "eagle-import") (part "CONN_05X2SHD_LOCK"))
    )
    (comp (ref "JP5")
      (value "PINHD-1X1")
      (footprint "eagle-import:1X01")
      (libsource (lib "eagle-import") (part "PINHD-1X1"))
    )
    (comp (ref "JP6")
      (value "PINHD-1X1")
      (footprint "eagle-import:1X01")
      (libsource (lib "eagle-import") (part "PINHD-1X1"))
    )
    (comp (ref "L")
      (value "YELLOW")
      (footprint "eagle-import:CHIP-LED0805")
      (libsource (lib "eagle-import") (part "led_LEDCHIP-LED0805"))
    )
    (comp (ref "L1")
      (value "39nH")
      (footprint "eagle-import:0603")
      (libsource (lib "eagle-import") (part "INDUCTOR0603"))
    )
    (comp (ref "L2")
      (value "68uH")
      (footprint "eagle-import:CD75")
      (libsource (lib "eagle-import") (part "L_CD75"))
    )
    (comp (ref "L3")
      (value "39nH")
      (footprint "eagle-import:0603")
      (libsource (lib "eagle-import") (part "INDUCTOR0603"))
    )
    (comp (ref "LED1")
      (value "0802 SIDE EMITTING LED RED")
      (footprint "eagle-import:CHIPLED_0805")
      (libsource (lib "eagle-import") (part "LEDCHIPLED_0805"))
    )
    (comp (ref "LED2")
      (value "0802 SIDE EMITTING LED RED")
      (footprint "eagle-import:CHIPLED_0805")
      (libsource (lib "eagle-import") (part "LEDCHIPLED_0805"))
    )
    (comp (ref "LED3")
      (value "0802 SIDE EMITTING LED RED")
      (footprint "eagle-import:CHIPLED_0805")
      (libsource (lib "eagle-import") (part "LEDCHIPLED_0805"))
    )
    (comp (ref "LED4")
      (value "0802 SIDE EMITTING LED RED")
      (footprint "eagle-import:CHIPLED_0805")
      (libsource (lib "eagle-import") (part "LEDCHIPLED_0805"))
    )
    (comp (ref "LED6")
      (value "0802 SIDE EMITTING LED GREEN")
      (footprint "eagle-import:LED3MM")
      (libsource (lib "eagle-import") (part "LED3MM"))
    )
    (comp (ref "MOS2")
      (value "IRLR024")
      (footprint "eagle-import:D2PACK")
      (libsource (lib "eagle-import") (part "N-POWER-MOSFETD2PAK-MOSFET"))
    )
    (comp (ref "ON")
      (value "GREEN")
      (footprint "eagle-import:CHIP-LED0805")
      (libsource (lib "eagle-import") (part "led_LEDCHIP-LED0805"))
    )
    (comp (ref "PWRIN")
      (value "Phoenix Pluggable 5.08mm 2 way")
      (footprint "eagle-import:MSTBA2")
      (fields (field (name "MF") "FARNELL") (field (name "MPN") "1757242"))
      (libsource (lib "eagle-import") (part "MSTBA2"))
    )
    (comp (ref "Q1")
      (value "IRLR024")
      (footprint "eagle-import:D-PAK_TO252AA")
      (libsource (lib "eagle-import") (part "N-POWER-MOSFETDPAK-MOSFET"))
    )
    (comp (ref "Q2")
      (value "IRLR024")
      (footprint "eagle-import:D-PAK_TO252AA")
      (libsource (lib "eagle-import") (part "N-POWER-MOSFETDPAK-MOSFET"))
    )
    (comp (ref "Q3")
      (value "16MHz")
      (footprint "eagle-import:QS")
      (libsource (lib "eagle-import") (part "XTAL/S"))
    )
    (comp (ref "Q22")
      (value "IRLR024")
      (footprint "eagle-import:D-PAK_TO252AA")
      (libsource (lib "eagle-import") (part "N-POWER-MOSFETDPAK-MOSFET"))
    )
    (comp (ref "R1")
      (value "3K6")
      (footprint "eagle-import:R0603")
      (libsource (lib "eagle-import") (part "resistor_348_R-EU_R0603"))
    )
    (comp (ref "R2")
      (value "4K7")
      (footprint "eagle-import:R0603")
      (libsource (lib "eagle-import") (part "rcl_R-EU_R0603"))
    )
    (comp (ref "R3")
      (value "10K")
      (footprint "eagle-import:B25P")
      (libsource (lib "eagle-import") (part "TRIM_EU-B25P"))
    )
    (comp (ref "R4")
      (value "10K")
      (footprint "eagle-import:B25P")
      (libsource (lib "eagle-import") (part "TRIM_EU-B25P"))
    )
    (comp (ref "R5")
      (value "3K6")
      (footprint "eagle-import:R0603")
      (libsource (lib "eagle-import") (part "resistor_348_R-EU_R0603"))
    )
    (comp (ref "R6")
      (value "10k")
      (footprint "eagle-import:R0603")
      (libsource (lib "eagle-import") (part "resistor_348_R-EU_R0603"))
    )
    (comp (ref "R7")
      (value "3K6")
      (footprint "eagle-import:R0603")
      (libsource (lib "eagle-import") (part "resistor_348_R-EU_R0603"))
    )
    (comp (ref "R8")
      (value "10k")
      (footprint "eagle-import:R0603")
      (libsource (lib "eagle-import") (part "resistor_348_R-EU_R0603"))
    )
    (comp (ref "R9")
      (value "10k")
      (footprint "eagle-import:R0603")
      (libsource (lib "eagle-import") (part "resistor_348_R-EU_R0603"))
    )
    (comp (ref "R10")
      (value "0.22R 3212")
      (footprint "eagle-import:R1210")
      (libsource (lib "eagle-import") (part "resistor_348_R-EU_R1210"))
    )
    (comp (ref "R11")
      (value "0.22R 3212")
      (footprint "eagle-import:R1210")
      (libsource (lib "eagle-import") (part "resistor_348_R-EU_R1210"))
    )
    (comp (ref "R12")
      (value "6K8")
      (footprint "eagle-import:R0603")
      (libsource (lib "eagle-import") (part "resistor_348_R-EU_R0603"))
    )
    (comp (ref "R13")
      (value "10k")
      (footprint "eagle-import:R0603")
      (libsource (lib "eagle-import") (part "resistor_348_R-EU_R0603"))
    )
    (comp (ref "R14")
      (value "10k")
      (footprint "eagle-import:R0603")
      (libsource (lib "eagle-import") (part "resistor_348_R-EU_R0603"))
    )
    (comp (ref "R15")
      (value "10k")
      (footprint "eagle-import:R0603")
      (libsource (lib "eagle-import") (part "resistor_348_R-EU_R0603"))
    )
    (comp (ref "R16")
      (value "10k")
      (footprint "eagle-import:R0603")
      (libsource (lib "eagle-import") (part "resistor_348_R-EU_R0603"))
    )
    (comp (ref "R17")
      (value "3K6")
      (footprint "eagle-import:R0603")
      (libsource (lib "eagle-import") (part "resistor_348_R-EU_R0603"))
    )
    (comp (ref "R18")
      (value "5K1")
      (footprint "eagle-import:R0603")
      (libsource (lib "eagle-import") (part "resistor_348_R-EU_R0603"))
    )
    (comp (ref "R19")
      (value "5K1")
      (footprint "eagle-import:R0603")
      (libsource (lib "eagle-import") (part "resistor_348_R-EU_R0603"))
    )
    (comp (ref "R20")
      (value "10K")
      (footprint "eagle-import:B25P")
      (libsource (lib "eagle-import") (part "TRIM_EU-B25P"))
    )
    (comp (ref "R21")
      (value "10K")
      (footprint "eagle-import:B25P")
      (libsource (lib "eagle-import") (part "TRIM_EU-B25P"))
    )
    (comp (ref "R22")
      (value "5K1")
      (footprint "eagle-import:R0603")
      (libsource (lib "eagle-import") (part "resistor_348_R-EU_R0603"))
    )
    (comp (ref "R23")
      (value "5K1")
      (footprint "eagle-import:R0603")
      (libsource (lib "eagle-import") (part "resistor_348_R-EU_R0603"))
    )
    (comp (ref "R24")
      (value "10r")
      (footprint "eagle-import:R0603")
      (libsource (lib "eagle-import") (part "resistor_R-EU_R0603"))
    )
    (comp (ref "R25")
      (value "100k")
      (footprint "eagle-import:R0603")
      (libsource (lib "eagle-import") (part "resistor_R-EU_R0603"))
    )
    (comp (ref "R26")
      (value "4k7")
      (footprint "eagle-import:R0603")
      (libsource (lib "eagle-import") (part "resistor_R-US_R0603"))
    )
    (comp (ref "R27")
      (value "4k7")
      (footprint "eagle-import:R0603")
      (libsource (lib "eagle-import") (part "resistor_R-US_R0603"))
    )
    (comp (ref "R28")
      (value "10R")
      (footprint "eagle-import:R0603@1")
      (libsource (lib "eagle-import") (part "R-US_R0603"))
    )
    (comp (ref "R29")
      (value "10k")
      (footprint "eagle-import:R0603")
      (libsource (lib "eagle-import") (part "resistor_348_R-EU_R0603"))
    )
    (comp (ref "R30")
      (value "0.22R 3212")
      (footprint "eagle-import:R1210")
      (libsource (lib "eagle-import") (part "resistor_348_R-EU_R1210"))
    )
    (comp (ref "R31")
      (value "0.22R 3212")
      (footprint "eagle-import:R1210")
      (libsource (lib "eagle-import") (part "resistor_348_R-EU_R1210"))
    )
    (comp (ref "R32")
      (value "6K8")
      (footprint "eagle-import:R0603")
      (libsource (lib "eagle-import") (part "resistor_348_R-EU_R0603"))
    )
    (comp (ref "R33")
      (value "10k")
      (footprint "eagle-import:R0603")
      (libsource (lib "eagle-import") (part "resistor_348_R-EU_R0603"))
    )
    (comp (ref "R34")
      (value "10k")
      (footprint "eagle-import:R0603")
      (libsource (lib "eagle-import") (part "resistor_348_R-EU_R0603"))
    )
    (comp (ref "R35")
      (value "10R")
      (footprint "eagle-import:R0603@1")
      (libsource (lib "eagle-import") (part "R-US_R0603"))
    )
    (comp (ref "R36")
      (value "10k")
      (footprint "eagle-import:R0603")
      (libsource (lib "eagle-import") (part "resistor_348_R-EU_R0603"))
    )
    (comp (ref "R37")
      (value "10k")
      (footprint "eagle-import:R0603")
      (libsource (lib "eagle-import") (part "resistor_348_R-EU_R0603"))
    )
    (comp (ref "R38")
      (value "10k")
      (footprint "eagle-import:R0603")
      (libsource (lib "eagle-import") (part "resistor_348_R-EU_R0603"))
    )
    (comp (ref "R39")
      (value "0.22R 3212")
      (footprint "eagle-import:R1210")
      (libsource (lib "eagle-import") (part "resistor_348_R-EU_R1210"))
    )
    (comp (ref "R40")
      (value "0.22R 3212")
      (footprint "eagle-import:R1210")
      (libsource (lib "eagle-import") (part "resistor_348_R-EU_R1210"))
    )
    (comp (ref "R41")
      (value "6K8")
      (footprint "eagle-import:R0603")
      (libsource (lib "eagle-import") (part "resistor_348_R-EU_R0603"))
    )
    (comp (ref "R42")
      (value "10k")
      (footprint "eagle-import:R0603")
      (libsource (lib "eagle-import") (part "resistor_348_R-EU_R0603"))
    )
    (comp (ref "R43")
      (value "10k")
      (footprint "eagle-import:R0603")
      (libsource (lib "eagle-import") (part "resistor_348_R-EU_R0603"))
    )
    (comp (ref "R44")
      (value "100k")
      (footprint "eagle-import:R0603")
      (libsource (lib "eagle-import") (part "resistor_348_R-EU_R0603"))
    )
    (comp (ref "R45")
      (value "10k")
      (footprint "eagle-import:R0603")
      (libsource (lib "eagle-import") (part "resistor_348_R-EU_R0603"))
    )
    (comp (ref "R46")
      (value "10k")
      (footprint "eagle-import:R0603")
      (libsource (lib "eagle-import") (part "resistor_348_R-EU_R0603"))
    )
    (comp (ref "R47")
      (value "10k")
      (footprint "eagle-import:R0603")
      (libsource (lib "eagle-import") (part "resistor_348_R-EU_R0603"))
    )
    (comp (ref "R48")
      (value "0.22R 3212")
      (footprint "eagle-import:R1210")
      (libsource (lib "eagle-import") (part "resistor_348_R-EU_R1210"))
    )
    (comp (ref "R49")
      (value "0.22R 3212")
      (footprint "eagle-import:R1210")
      (libsource (lib "eagle-import") (part "resistor_348_R-EU_R1210"))
    )
    (comp (ref "R50")
      (value "6K8")
      (footprint "eagle-import:R0603")
      (libsource (lib "eagle-import") (part "resistor_348_R-EU_R0603"))
    )
    (comp (ref "R51")
      (value "10k")
      (footprint "eagle-import:R0603")
      (libsource (lib "eagle-import") (part "resistor_348_R-EU_R0603"))
    )
    (comp (ref "R52")
      (value "10k")
      (footprint "eagle-import:R0603")
      (libsource (lib "eagle-import") (part "resistor_348_R-EU_R0603"))
    )
    (comp (ref "R53")
      (value "100k")
      (footprint "eagle-import:R0603")
      (libsource (lib "eagle-import") (part "resistor_348_R-EU_R0603"))
    )
    (comp (ref "R54")
      (value "27R")
      (footprint "eagle-import:R0603-ROUND")
      (libsource (lib "eagle-import") (part "R-EU_R0603"))
    )
    (comp (ref "R55")
      (value "1k")
      (footprint "eagle-import:R0603")
      (libsource (lib "eagle-import") (part "rcl_334_R-EU_R0603"))
    )
    (comp (ref "R56")
      (value "330")
      (footprint "eagle-import:0603-RES")
      (libsource (lib "eagle-import") (part "330OHM1/10W1%(0603)"))
    )
    (comp (ref "R57")
      (value "330")
      (footprint "eagle-import:0603-RES")
      (libsource (lib "eagle-import") (part "330OHM1/10W1%(0603)"))
    )
    (comp (ref "R58")
      (value "330")
      (footprint "eagle-import:0603-RES")
      (libsource (lib "eagle-import") (part "330OHM1/10W1%(0603)"))
    )
    (comp (ref "R59")
      (value "330")
      (footprint "eagle-import:0603-RES")
      (libsource (lib "eagle-import") (part "330OHM1/10W1%(0603)"))
    )
    (comp (ref "R60")
      (value "1k")
      (footprint "eagle-import:R0603")
      (libsource (lib "eagle-import") (part "rcl_334_R-EU_R0603"))
    )
    (comp (ref "R61")
      (value "10k")
      (footprint "eagle-import:R0603")
      (libsource (lib "eagle-import") (part "rcl_334_R-EU_R0603"))
    )
    (comp (ref "R62")
      (value "10R")
      (footprint "eagle-import:R0603")
      (libsource (lib "eagle-import") (part "resistor_R-EU_R0603"))
    )
    (comp (ref "R63")
      (value "100k")
      (footprint "eagle-import:R0603")
      (libsource (lib "eagle-import") (part "resistor_R-EU_R0603"))
    )
    (comp (ref "R64")
      (value "10k")
      (footprint "eagle-import:R0603")
      (libsource (lib "eagle-import") (part "rcl_334_R-EU_R0603"))
    )
    (comp (ref "R65")
      (value "10k")
      (footprint "eagle-import:R0603")
      (libsource (lib "eagle-import") (part "rcl_334_R-EU_R0603"))
    )
    (comp (ref "R66")
      (value "10k")
      (footprint "eagle-import:R0603")
      (libsource (lib "eagle-import") (part "rcl_334_R-EU_R0603"))
    )
    (comp (ref "R67")
      (value "10k")
      (footprint "eagle-import:R0603")
      (libsource (lib "eagle-import") (part "rcl_334_R-EU_R0603"))
    )
    (comp (ref "R68")
      (value "1k")
      (footprint "eagle-import:R0603")
      (libsource (lib "eagle-import") (part "rcl_334_R-EU_R0603"))
    )
    (comp (ref "R69")
      (value "1k")
      (footprint "eagle-import:R0603")
      (libsource (lib "eagle-import") (part "rcl_334_R-EU_R0603"))
    )
    (comp (ref "R70")
      (value "5.1k")
      (footprint "eagle-import:0603@1")
      (libsource (lib "eagle-import") (part "5.1KOHM5.1KOHM-0603-1/10W-1%"))
    )
    (comp (ref "R71")
      (value "5.1k")
      (footprint "eagle-import:0603@1")
      (libsource (lib "eagle-import") (part "5.1KOHM5.1KOHM-0603-1/10W-1%"))
    )
    (comp (ref "R72")
      (value "1K")
      (footprint "eagle-import:0603-RES")
      (libsource (lib "eagle-import") (part "RESISTOR0603-RES"))
    )
    (comp (ref "R73")
      (value "1K")
      (footprint "eagle-import:0603-RES")
      (libsource (lib "eagle-import") (part "RESISTOR0603-RES"))
    )
    (comp (ref "R74")
      (value "1K")
      (footprint "eagle-import:R0603")
      (libsource (lib "eagle-import") (part "resistor_R-US_R0603"))
    )
    (comp (ref "R75")
      (value "1K")
      (footprint "eagle-import:R0603")
      (libsource (lib "eagle-import") (part "resistor_R-US_R0603"))
    )
    (comp (ref "R76")
      (value "1K")
      (footprint "eagle-import:R0603")
      (libsource (lib "eagle-import") (part "resistor_R-US_R0603"))
    )
    (comp (ref "R77")
      (value "1K")
      (footprint "eagle-import:R0603")
      (libsource (lib "eagle-import") (part "resistor_R-US_R0603"))
    )
    (comp (ref "R78")
      (value "10K")
      (footprint "eagle-import:R0603")
      (libsource (lib "eagle-import") (part "resistor_R-US_R0603"))
    )
    (comp (ref "R79")
      (value "10K")
      (footprint "eagle-import:R0603")
      (libsource (lib "eagle-import") (part "resistor_R-US_R0603"))
    )
    (comp (ref "R80")
      (value "10K")
      (footprint "eagle-import:R0603")
      (libsource (lib "eagle-import") (part "resistor_R-US_R0603"))
    )
    (comp (ref "R81")
      (value "10K")
      (footprint "eagle-import:R0603")
      (libsource (lib "eagle-import") (part "resistor_R-US_R0603"))
    )
    (comp (ref "RESET")
      (value "TS42")
      (footprint "eagle-import:TS42")
      (libsource (lib "eagle-import") (part "TS42"))
    )
    (comp (ref "SJ1") (value "SJ") (footprint "eagle-import:SJ") (libsource (lib "eagle-import") (part "SJ")))
    (comp (ref "SJ2") (value "SJ") (footprint "eagle-import:SJ") (libsource (lib "eagle-import") (part "SJ")))
    (comp (ref "SJ3") (value "SJ") (footprint "eagle-import:SJ") (libsource (lib "eagle-import") (part "SJ")))
    (comp (ref "SJ4") (value "SJ") (footprint "eagle-import:SJ") (libsource (lib "eagle-import") (part "SJ")))
    (comp (ref "SJ5") (value "SJ") (footprint "eagle-import:SJ") (libsource (lib "eagle-import") (part "SJ")))
    (comp (ref "SJ6") (value "SJ") (footprint "eagle-import:SJ") (libsource (lib "eagle-import") (part "SJ")))
    (comp (ref "SJ7") (value "SJ") (footprint "eagle-import:SJ") (libsource (lib "eagle-import") (part "SJ")))
    (comp (ref "SJ8") (value "SJ") (footprint "eagle-import:SJ") (libsource (lib "eagle-import") (part "SJ")))
    (comp (ref "T2")
      (value "FDN340P")
      (footprint "eagle-import:SOT-23")
      (libsource (lib "eagle-import") (part "PMOSSOT23"))
    )
    (comp (ref "U$1")
      (value "TB67S109AFNG")
      (footprint "eagle-import:TB67S109AFTG-HTSSPO48-P-300-0.50")
      (libsource (lib "eagle-import") (part "TB67S109AFTG"))
    )
    (comp (ref "U$2")
      (value "TB67S109AFNG")
      (footprint "eagle-import:TB67S109AFTG-HTSSPO48-P-300-0.50")
      (libsource (lib "eagle-import") (part "TB67S109AFTG"))
    )
    (comp (ref "U$4")
      (value "ATQ-FUSE")
      (footprint "eagle-import:ATQ-FUSE")
      (libsource (lib "eagle-import") (part "ATQ-FUSE"))
    )
    (comp (ref "U$7")
      (value "TB67S109AFNG")
      (footprint "eagle-import:TB67S109AFTG-HTSSPO48-P-300-0.50")
      (libsource (lib "eagle-import") (part "TB67S109AFTG"))
    )
    (comp (ref "U$17")
      (value "TB67S109AFNG")
      (footprint "eagle-import:TB67S109AFTG-HTSSPO48-P-300-0.50")
      (libsource (lib "eagle-import") (part "TB67S109AFTG"))
    )
    (comp (ref "U1")
      (value "TLP291-4")
      (footprint "eagle-import:SO16_TOS")
      (fields (field (name "COPYRIGHT") "Copyright (C) 2018 Accelerated Designs. All rights reserved"))
      (libsource (lib "eagle-import") (part "TLP291-4"))
    )
    (comp (ref "U2")
      (value "USD-SOCKETUSD")
      (footprint "eagle-import:USD-SOCKET-PP")
      (libsource (lib "eagle-import") (part "USD-SOCKETUSD"))
    )
    (comp (ref "U6")
      (value "FT232RLSSOP")
      (footprint "eagle-import:SSOP28DB")
      (libsource (lib "eagle-import") (part "FT232RLSSOP"))
    )
    (comp (ref "X-END1")
      (value "Phoenix Pluggable 3.81mm 2 way")
      (footprint "eagle-import:MC1.5_2-G-3.81")
      (libsource (lib "eagle-import") (part "MC1.5/2"))
    )
    (comp (ref "X-END2")
      (value "Phoenix Pluggable 3.81mm 2 way")
      (footprint "eagle-import:MC1.5_2-G-3.81")
      (libsource (lib "eagle-import") (part "MC1.5/2"))
    )
    (comp (ref "X-END3")
      (value "Phoenix Pluggable 3.81mm 2 way")
      (footprint "eagle-import:MC1.5_2-G-3.81")
      (libsource (lib "eagle-import") (part "MC1.5/2"))
    )
    (comp (ref "Z-CONN1")
      (value "CONN_05X2SHD_LOCK")
      (footprint "eagle-import:2X5-SHROUDED_LOCK")
      (libsource (lib "eagle-import") (part "CONN_05X2SHD_LOCK"))
    )
  )
  (nets
    (net (code "1") (name "+3V3") (class "Default")
      (node (ref "C28") (pin "2") (pinfunction "2_2") (pintype "passive"))
      (node (ref "C47") (pin "A") (pinfunction "+_A") (pintype "passive"))
      (node (ref "C49") (pin "1") (pinfunction "1_1") (pintype "passive"))
      (node (ref "C50") (pin "1") (pinfunction "1_1") (pintype "passive"))
      (node (ref "C52") (pin "A") (pinfunction "+_A") (pintype "passive"))
      (node (ref "IC1") (pin "1") (pinfunction "VDD_1") (pintype "power_in"))
      (node (ref "IC2") (pin "4") (pinfunction "OUT_4") (pintype "passive"))
      (node (ref "IC5") (pin "6") (pinfunction "-IN_6") (pintype "input"))
      (node (ref "U2") (pin "4") (pinfunction "VCC_4") (pintype "bidirectional"))
    )
    (net (code "2") (name "3VUSB") (class "Default")
      (node (ref "C45") (pin "1") (pinfunction "1_1") (pintype "passive"))
      (node (ref "U6") (pin "17") (pinfunction "3V3OUT_17") (pintype "output"))
    )
    (net (code "3") (name "5-GND") (class "Default")
      (node (ref "RESET") (pin "5") (pinfunction "5-GND_5") (pintype "power_in"))
    )
    (net (code "4") (name "5VREG") (class "Default")
      (node (ref "C15") (pin "1") (pinfunction "1_1") (pintype "passive"))
      (node (ref "C20") (pin "1") (pinfunction "1_1") (pintype "passive"))
      (node (ref "C25") (pin "1") (pinfunction "1_1") (pintype "passive"))
      (node (ref "C30") (pin "2") (pinfunction "2_2") (pintype "passive"))
      (node (ref "C51") (pin "A") (pinfunction "+_A") (pintype "passive"))
      (node (ref "C56") (pin "+") (pinfunction "+_+") (pintype "passive"))
      (node (ref "C6") (pin "1") (pinfunction "1_1") (pintype "passive"))
      (node (ref "C7") (pin "1") (pinfunction "1_1") (pintype "passive"))
      (node (ref "C8") (pin "1") (pinfunction "1_1") (pintype "passive"))
      (node (ref "C9") (pin "1") (pinfunction "1_1") (pintype "passive"))
      (node (ref "IC2") (pin "3") (pinfunction "IN_3") (pintype "input"))
      (node (ref "IC3") (pin "10") (pinfunction "VCC_10") (pintype "power_in"))
      (node (ref "IC3") (pin "100") (pinfunction "AVCC_100") (pintype "power_in"))
      (node (ref "IC3") (pin "31") (pinfunction "VCC1_31") (pintype "power_in"))
      (node (ref "IC3") (pin "61") (pinfunction "VCC2_61") (pintype "power_in"))
      (node (ref "IC3") (pin "80") (pinfunction "VCC3_80") (pintype "power_in"))
      (node (ref "IC5") (pin "8") (pinfunction "V+_8") (pintype "power_in"))
      (node (ref "IC9") (pin "3") (pinfunction "FB_3") (pintype "bidirectional"))
      (node (ref "ICSP") (pin "2") (pinfunction "2_2") (pintype "passive"))
      (node (ref "JP6") (pin "1") (pinfunction "1_1") (pintype "passive"))
      (node (ref "L1") (pin "2") (pinfunction "2_2") (pintype "passive"))
      (node (ref "L2") (pin "1") (pinfunction "1_1") (pintype "passive"))
      (node (ref "LED1") (pin "C") (pinfunction "C_C") (pintype "passive"))
      (node (ref "LED2") (pin "C") (pinfunction "C_C") (pintype "passive"))
      (node (ref "LED3") (pin "C") (pinfunction "C_C") (pintype "passive"))
      (node (ref "LED4") (pin "C") (pinfunction "C_C") (pintype "passive"))
      (node (ref "R12") (pin "2") (pinfunction "2_2") (pintype "passive"))
      (node (ref "R13") (pin "2") (pinfunction "2_2") (pintype "passive"))
      (node (ref "R14") (pin "2") (pinfunction "2_2") (pintype "passive"))
      (node (ref "R15") (pin "2") (pinfunction "2_2") (pintype "passive"))
      (node (ref "R16") (pin "2") (pinfunction "2_2") (pintype "passive"))
      (node (ref "R18") (pin "2") (pinfunction "2_2") (pintype "passive"))
      (node (ref "R19") (pin "2") (pinfunction "2_2") (pintype "passive"))
      (node (ref "R22") (pin "2") (pinfunction "2_2") (pintype "passive"))
      (node (ref "R23") (pin "2") (pinfunction "2_2") (pintype "passive"))
      (node (ref "R29") (pin "2") (pinfunction "2_2") (pintype "passive"))
      (node (ref "R32") (pin "2") (pinfunction "2_2") (pintype "passive"))
      (node (ref "R33") (pin "2") (pinfunction "2_2") (pintype "passive"))
      (node (ref "R34") (pin "2") (pinfunction "2_2") (pintype "passive"))
      (node (ref "R36") (pin "2") (pinfunction "2_2") (pintype "passive"))
      (node (ref "R37") (pin "2") (pinfunction "2_2") (pintype "passive"))
      (node (ref "R38") (pin "2") (pinfunction "2_2") (pintype "passive"))
      (node (ref "R41") (pin "2") (pinfunction "2_2") (pintype "passive"))
      (node (ref "R42") (pin "2") (pinfunction "2_2") (pintype "passive"))
      (node (ref "R43") (pin "2") (pinfunction "2_2") (pintype "passive"))
      (node (ref "R45") (pin "2") (pinfunction "2_2") (pintype "passive"))
      (node (ref "R46") (pin "2") (pinfunction "2_2") (pintype "passive"))
      (node (ref "R47") (pin "2") (pinfunction "2_2") (pintype "passive"))
      (node (ref "R50") (pin "2") (pinfunction "2_2") (pintype "passive"))
      (node (ref "R51") (pin "2") (pinfunction "2_2") (pintype "passive"))
      (node (ref "R52") (pin "2") (pinfunction "2_2") (pintype "passive"))
      (node (ref "R6") (pin "2") (pinfunction "2_2") (pintype "passive"))
      (node (ref "R60") (pin "1") (pinfunction "1_1") (pintype "passive"))
      (node (ref "R61") (pin "2") (pinfunction "2_2") (pintype "passive"))
      (node (ref "R64") (pin "2") (pinfunction "2_2") (pintype "passive"))
      (node (ref "R65") (pin "2") (pinfunction "2_2") (pintype "passive"))
      (node (ref "R74") (pin "1") (pinfunction "1_1") (pintype "passive"))
      (node (ref "R75") (pin "1") (pinfunction "1_1") (pintype "passive"))
      (node (ref "R76") (pin "1") (pinfunction "1_1") (pintype "passive"))
      (node (ref "R77") (pin "1") (pinfunction "1_1") (pintype "passive"))
      (node (ref "R78") (pin "2") (pinfunction "2_2") (pintype "passive"))
      (node (ref "R79") (pin "2") (pinfunction "2_2") (pintype "passive"))
      (node (ref "R8") (pin "2") (pinfunction "2_2") (pintype "passive"))
      (node (ref "R80") (pin "2") (pinfunction "2_2") (pintype "passive"))
      (node (ref "R81") (pin "2") (pinfunction "2_2") (pintype "passive"))
      (node (ref "R9") (pin "2") (pinfunction "2_2") (pintype "passive"))
      (node (ref "T2") (pin "2") (pinfunction "S_2") (pintype "passive"))
    )
    (net (code "5") (name "AGND") (class "Default")
      (node (ref "BEDTH") (pin "1") (pinfunction "1_1") (pintype "passive"))
      (node (ref "C3") (pin "C") (pinfunction "-_C") (pintype "passive"))
      (node (ref "C4") (pin "C") (pinfunction "-_C") (pintype "passive"))
      (node (ref "ETHERM") (pin "1") (pinfunction "1_1") (pintype "passive"))
      (node (ref "J1") (pin "9") (pinfunction "9_9") (pintype "passive"))
      (node (ref "L3") (pin "1") (pinfunction "1_1") (pintype "passive"))
    )
    (net (code "6") (name "AREF") (class "Default")
      (node (ref "C5") (pin "1") (pinfunction "1_1") (pintype "passive"))
      (node (ref "IC3") (pin "98") (pinfunction "AREF_98") (pintype "bidirectional"))
    )
    (net (code "7") (name "AVCC") (class "Default")
      (node (ref "L1") (pin "1") (pinfunction "1_1") (pintype "passive"))
      (node (ref "R26") (pin "1") (pinfunction "1_1") (pintype "passive"))
      (node (ref "R27") (pin "1") (pinfunction "1_1") (pintype "passive"))
    )
    (net (code "8") (name "BED-NEG1") (class "Default")
      (node (ref "BED") (pin "1") (pinfunction "1_1") (pintype "passive"))
      (node (ref "D2") (pin "A") (pinfunction "A_A") (pintype "passive"))
      (node (ref "MOS2") (pin "2") (pinfunction "D_2") (pintype "passive"))
    )
    (net (code "9") (name "CMP") (class "Default")
      (node (ref "C29") (pin "2") (pinfunction "2_2") (pintype "passive"))
      (node (ref "IC5") (pin "5") (pinfunction "+IN_5") (pintype "input"))
      (node (ref "R66") (pin "1") (pinfunction "1_1") (pintype "passive"))
      (node (ref "R67") (pin "2") (pinfunction "2_2") (pintype "passive"))
    )
    (net (code "10") (name "CS") (class "Default")
      (node (ref "IC1") (pin "2") (pinfunction "O_2") (pintype "output"))
      (node (ref "U2") (pin "2") (pinfunction "CS_2") (pintype "bidirectional"))
    )
    (net (code "11") (name "CTS") (class "Default")
      (node (ref "U6") (pin "11") (pinfunction "CTS_11") (pintype "input"))
    )
    (net (code "12") (name "D+1") (class "Default")
      (node (ref "J3") (pin "A6") (pinfunction "D+_A6") (pintype "bidirectional"))
      (node (ref "J3") (pin "B6") (pinfunction "D+_B6") (pintype "bidirectional"))
      (node (ref "U6") (pin "15") (pinfunction "USBDP_15") (pintype "bidirectional"))
    )
    (net (code "13") (name "D-1") (class "Default")
      (node (ref "J3") (pin "A7") (pinfunction "D-_A7") (pintype "bidirectional"))
      (node (ref "J3") (pin "B7") (pinfunction "D-_B7") (pintype "bidirectional"))
      (node (ref "U6") (pin "16") (pinfunction "USBDM_16") (pintype "bidirectional"))
    )
    (net (code "14") (name "D0") (class "Default")
      (node (ref "IC3") (pin "2") (pinfunction "(RXD0/PCIN8)PE0_2") (pintype "bidirectional"))
      (node (ref "R68") (pin "2") (pinfunction "2_2") (pintype "passive"))
    )
    (net (code "15") (name "D1") (class "Default")
      (node (ref "IC3") (pin "3") (pinfunction "(TXD0)PE1_3") (pintype "bidirectional"))
      (node (ref "R69") (pin "2") (pinfunction "2_2") (pintype "passive"))
    )
    (net (code "16") (name "D2{slash}EENABLE") (class "Default")
      (node (ref "IC3") (pin "6") (pinfunction "(OC3B/INT4)PE4_6") (pintype "bidirectional"))
      (node (ref "U$7") (pin "ENABLE") (pinfunction "ENABLE_ENABLE") (pintype "bidirectional"))
    )
    (net (code "17") (name "D3") (class "Default")
      (node (ref "IC3") (pin "7") (pinfunction "(OC3C/INT5)PE5_7") (pintype "bidirectional"))
      (node (ref "R78") (pin "1") (pinfunction "1_1") (pintype "passive"))
      (node (ref "U1") (pin "16") (pinfunction "16_16") (pintype "passive"))
    )
    (net (code "18") (name "D4{slash}EDIR") (class "Default")
      (node (ref "IC3") (pin "1") (pinfunction "(OC0B)PG5_1") (pintype "bidirectional"))
      (node (ref "U$7") (pin "CS/CCW") (pinfunction "CW/CCW_CS/CCW") (pintype "bidirectional"))
    )
    (net (code "19") (name "D5{slash}ESTEP") (class "Default")
      (node (ref "IC3") (pin "5") (pinfunction "(OC3A/AIN1)PE3_5") (pintype "bidirectional"))
      (node (ref "U$7") (pin "CLK") (pinfunction "CLK_CLK") (pintype "bidirectional"))
    )
    (net (code "20") (name "D6") (class "Default")
      (node (ref "IC3") (pin "8") (pinfunction "(T3/INT6)PE6_8") (pintype "bidirectional"))
    )
    (net (code "21") (name "D7") (class "Default")
      (node (ref "IC3") (pin "9") (pinfunction "(CLKO/ICP3/INT7)PE7_9") (pintype "bidirectional"))
    )
    (net (code "22") (name "D8") (class "Default")
      (node (ref "IC3") (pin "17") (pinfunction "PH5(OC4C)_17") (pintype "bidirectional"))
      (node (ref "R79") (pin "1") (pinfunction "1_1") (pintype "passive"))
      (node (ref "U1") (pin "14") (pinfunction "14_14") (pintype "passive"))
    )
    (net (code "23") (name "D9") (class "Default")
      (node (ref "IC3") (pin "18") (pinfunction "PH6(OC2B)_18") (pintype "bidirectional"))
      (node (ref "R80") (pin "1") (pinfunction "1_1") (pintype "passive"))
      (node (ref "U1") (pin "12") (pinfunction "12_12") (pintype "passive"))
    )
    (net (code "24") (name "D10") (class "Default")
      (node (ref "IC3") (pin "23") (pinfunction "(OC2A/PCINT4)PB4_23") (pintype "bidirectional"))
      (node (ref "R81") (pin "1") (pinfunction "1_1") (pintype "passive"))
      (node (ref "U1") (pin "10") (pinfunction "10_10") (pintype "passive"))
    )
    (net (code "25") (name "D11") (class "Default")
      (node (ref "IC3") (pin "24") (pinfunction "(OC1A/PCINT5)PB5_24") (pintype "bidirectional"))
    )
    (net (code "26") (name "D12") (class "Default")
      (node (ref "IC3") (pin "25") (pinfunction "(OC1B/PCINT6)PB6_25") (pintype "bidirectional"))
    )
    (net (code "27") (name "D13") (class "Default")
      (node (ref "IC3") (pin "26") (pinfunction "(OC0A/OC1C/PCINT7)PB7_26") (pintype "bidirectional"))
      (node (ref "R55") (pin "1") (pinfunction "1_1") (pintype "passive"))
    )
    (net (code "28") (name "D14{slash}TXD3") (class "Default")
      (node (ref "IC3") (pin "64") (pinfunction "PJ1(TXD3/PCINT10)_64") (pintype "bidirectional"))
    )
    (net (code "29") (name "D15{slash}RXD3") (class "Default")
      (node (ref "IC3") (pin "63") (pinfunction "PJ0(RXD3/PCINT9)_63") (pintype "bidirectional"))
    )
    (net (code "30") (name "D16{slash}TXD2") (class "Default")
      (node (ref "IC3") (pin "13") (pinfunction "PH1(TXD2)_13") (pintype "bidirectional"))
    )
    (net (code "31") (name "D17{slash}RXD2") (class "Default")
      (node (ref "IC3") (pin "12") (pinfunction "PH0(RXD2)_12") (pintype "bidirectional"))
    )
    (net (code "32") (name "D18{slash}TXD1") (class "Default")
      (node (ref "IC3") (pin "46") (pinfunction "(TXD1/INT3)PD3_46") (pintype "bidirectional"))
    )
    (net (code "33") (name "D19{slash}RXD1") (class "Default")
      (node (ref "IC3") (pin "45") (pinfunction "(RXD1/INT2)PD2_45") (pintype "bidirectional"))
    )
    (net (code "34") (name "D20{slash}SDA") (class "Default")
      (node (ref "IC3") (pin "44") (pinfunction "(SDA/INT1)PD1_44") (pintype "bidirectional"))
      (node (ref "R65") (pin "1") (pinfunction "1_1") (pintype "passive"))
    )
    (net (code "35") (name "D21{slash}SCL") (class "Default")
      (node (ref "IC3") (pin "43") (pinfunction "(SCL/INT0)PD0_43") (pintype "bidirectional"))
      (node (ref "R64") (pin "1") (pinfunction "1_1") (pintype "passive"))
    )
    (net (code "36") (name "D22") (class "Default")
      (node (ref "IC3") (pin "78") (pinfunction "(AD0)PA0_78") (pintype "bidirectional"))
    )
    (net (code "37") (name "D23") (class "Default")
      (node (ref "IC3") (pin "77") (pinfunction "(AD1)PA1_77") (pintype "bidirectional"))
    )
    (net (code "38") (name "D24") (class "Default")
      (node (ref "IC3") (pin "76") (pinfunction "(AD2)PA2_76") (pintype "bidirectional"))
    )
    (net (code "39") (name "D25") (class "Default")
      (node (ref "IC3") (pin "75") (pinfunction "(AD3)PA3_75") (pintype "bidirectional"))
    )
    (net (code "40") (name "D26") (class "Default")
      (node (ref "IC3") (pin "74") (pinfunction "(AD4)PA4_74") (pintype "bidirectional"))
    )
    (net (code "41") (name "D27") (class "Default")
      (node (ref "IC3") (pin "73") (pinfunction "(AD5)PA5_73") (pintype "bidirectional"))
    )
    (net (code "42") (name "D28") (class "Default")
      (node (ref "IC3") (pin "72") (pinfunction "(AD6)PA6_72") (pintype "bidirectional"))
    )
    (net (code "43") (name "D29") (class "Default")
      (node (ref "IC3") (pin "71") (pinfunction "(AD7)PA7_71") (pintype "bidirectional"))
    )
    (net (code "44") (name "D30") (class "Default")
      (node (ref "IC3") (pin "60") (pinfunction "(A15)PC7_60") (pintype "bidirectional"))
    )
    (net (code "45") (name "D31") (class "Default")
      (node (ref "IC3") (pin "59") (pinfunction "(A14)PC6_59") (pintype "bidirectional"))
    )
    (net (code "46") (name "D32") (class "Default")
      (node (ref "IC3") (pin "58") (pinfunction "(A13)PC5_58") (pintype "bidirectional"))
    )
    (net (code "47") (name "D33") (class "Default")
      (node (ref "IC3") (pin "57") (pinfunction "(A12)PC4_57") (pintype "bidirectional"))
    )
    (net (code "48") (name "D34") (class "Default")
      (node (ref "IC3") (pin "56") (pinfunction "(A11)PC3_56") (pintype "bidirectional"))
    )
    (net (code "49") (name "D35") (class "Default")
      (node (ref "IC3") (pin "55") (pinfunction "(A10)PC2_55") (pintype "bidirectional"))
    )
    (net (code "50") (name "D36") (class "Default")
      (node (ref "IC3") (pin "54") (pinfunction "(A9)PC1_54") (pintype "bidirectional"))
    )
    (net (code "51") (name "D37") (class "Default")
      (node (ref "IC3") (pin "53") (pinfunction "(A8)PC0_53") (pintype "bidirectional"))
    )
    (net (code "52") (name "D38") (class "Default")
      (node (ref "IC3") (pin "50") (pinfunction "(T0)PD7_50") (pintype "bidirectional"))
    )
    (net (code "53") (name "D39") (class "Default")
      (node (ref "IC3") (pin "70") (pinfunction "(ALE)PG2_70") (pintype "bidirectional"))
    )
    (net (code "54") (name "D40") (class "Default")
      (node (ref "IC3") (pin "52") (pinfunction "(RD)PG1_52") (pintype "bidirectional"))
    )
    (net (code "55") (name "D41") (class "Default")
      (node (ref "IC3") (pin "51") (pinfunction "(WR)PG0_51") (pintype "bidirectional"))
    )
    (net (code "56") (name "D42") (class "Default")
      (node (ref "IC3") (pin "42") (pinfunction "PL7_42") (pintype "bidirectional"))
    )
    (net (code "57") (name "D43") (class "Default")
      (node (ref "IC3") (pin "41") (pinfunction "PL6_41") (pintype "bidirectional"))
    )
    (net (code "58") (name "D44") (class "Default")
      (node (ref "IC3") (pin "40") (pinfunction "PL5(OC5C)_40") (pintype "bidirectional"))
    )
    (net (code "59") (name "D45") (class "Default")
      (node (ref "IC3") (pin "39") (pinfunction "PL4(OC5B)_39") (pintype "bidirectional"))
    )
    (net (code "60") (name "D46") (class "Default")
      (node (ref "IC3") (pin "38") (pinfunction "PL3(OC5A)_38") (pintype "bidirectional"))
    )
    (net (code "61") (name "D47") (class "Default")
      (node (ref "IC3") (pin "37") (pinfunction "PL2(T5)_37") (pintype "bidirectional"))
    )
    (net (code "62") (name "D48") (class "Default")
      (node (ref "IC3") (pin "36") (pinfunction "PL1(ICP5)_36") (pintype "bidirectional"))
    )
    (net (code "63") (name "D49") (class "Default")
      (node (ref "IC3") (pin "35") (pinfunction "PL0(ICP4)_35") (pintype "bidirectional"))
    )
    (net (code "64") (name "D50{slash}MISO") (class "Default")
      (node (ref "IC3") (pin "22") (pinfunction "(MISO/PCINT3)PB3_22") (pintype "bidirectional"))
      (node (ref "ICSP") (pin "1") (pinfunction "1_1") (pintype "passive"))
      (node (ref "U2") (pin "7") (pinfunction "DO_7") (pintype "bidirectional"))
    )
    (net (code "65") (name "D51{slash}MOSI") (class "Default")
      (node (ref "IC1") (pin "5") (pinfunction "I_5") (pintype "input"))
      (node (ref "IC3") (pin "21") (pinfunction "(MOSI/PCINT2)PB2_21") (pintype "bidirectional"))
      (node (ref "ICSP") (pin "4") (pinfunction "4_4") (pintype "passive"))
    )
    (net (code "66") (name "D52{slash}SCK") (class "Default")
      (node (ref "IC1") (pin "7") (pinfunction "I_7") (pintype "input"))
      (node (ref "IC3") (pin "20") (pinfunction "(SCK/PCINT1)PB1_20") (pintype "bidirectional"))
      (node (ref "ICSP") (pin "3") (pinfunction "3_3") (pintype "passive"))
    )
    (net (code "67") (name "D53{slash}SS") (class "Default")
      (node (ref "IC1") (pin "3") (pinfunction "I_3") (pintype "input"))
      (node (ref "IC3") (pin "19") (pinfunction "(SS/PCINT0)PB0_19") (pintype "bidirectional"))
    )
    (net (code "68") (name "D54{slash}ADC0") (class "Default")
      (node (ref "IC3") (pin "97") (pinfunction "(ADC0)PF0_97") (pintype "bidirectional"))
    )
    (net (code "69") (name "D55{slash}ADC1{slash}ZENABLE") (class "Default")
      (node (ref "IC3") (pin "96") (pinfunction "(ADC1)PF1_96") (pintype "bidirectional"))
      (node (ref "U$2") (pin "ENABLE") (pinfunction "ENABLE_ENABLE") (pintype "bidirectional"))
    )
    (net (code "70") (name "D56{slash}ADC2{slash}ZSTEP") (class "Default")
      (node (ref "IC3") (pin "95") (pinfunction "(ADC2)PF2_95") (pintype "bidirectional"))
      (node (ref "U$2") (pin "CLK") (pinfunction "CLK_CLK") (pintype "bidirectional"))
    )
    (net (code "71") (name "D57{slash}ADC3{slash}ZDIR") (class "Default")
      (node (ref "IC3") (pin "94") (pinfunction "(ADC3)PF3_94") (pintype "bidirectional"))
      (node (ref "U$2") (pin "CS/CCW") (pinfunction "CW/CCW_CS/CCW") (pintype "bidirectional"))
    )
    (net (code "72") (name "D58{slash}ADC4{slash}YENABLE") (class "Default")
      (node (ref "IC3") (pin "93") (pinfunction "(ADC4/TCK)PF4_93") (pintype "bidirectional"))
      (node (ref "U$1") (pin "ENABLE") (pinfunction "ENABLE_ENABLE") (pintype "bidirectional"))
    )
    (net (code "73") (name "D59{slash}ADC5{slash}YSTEP") (class "Default")
      (node (ref "IC3") (pin "92") (pinfunction "(ADC5/TMS)PF5_92") (pintype "bidirectional"))
      (node (ref "U$1") (pin "CLK") (pinfunction "CLK_CLK") (pintype "bidirectional"))
    )
    (net (code "74") (name "D60{slash}ADC6{slash}YDIR") (class "Default")
      (node (ref "IC3") (pin "91") (pinfunction "(ADC6/TDO)PF6_91") (pintype "bidirectional"))
      (node (ref "U$1") (pin "CS/CCW") (pinfunction "CW/CCW_CS/CCW") (pintype "bidirectional"))
    )
    (net (code "75") (name "D61{slash}ADC7{slash}XENABLE") (class "Default")
      (node (ref "IC3") (pin "90") (pinfunction "(ADC7/TDI)PF7_90") (pintype "bidirectional"))
      (node (ref "U$17") (pin "ENABLE") (pinfunction "ENABLE_ENABLE") (pintype "bidirectional"))
    )
    (net (code "76") (name "D62{slash}ADC8{slash}XSTEP") (class "Default")
      (node (ref "IC3") (pin "89") (pinfunction "PK0(ADC8/PCINT16)_89") (pintype "bidirectional"))
      (node (ref "U$17") (pin "CLK") (pinfunction "CLK_CLK") (pintype "bidirectional"))
    )
    (net (code "77") (name "D63{slash}ADC9{slash}XDIR") (class "Default")
      (node (ref "IC3") (pin "88") (pinfunction "PK1(ADC9/PCINT17)_88") (pintype "bidirectional"))
      (node (ref "U$17") (pin "CS/CCW") (pinfunction "CW/CCW_CS/CCW") (pintype "bidirectional"))
    )
    (net (code "78") (name "D64{slash}ADC10{slash}BED") (class "Default")
      (node (ref "IC3") (pin "87") (pinfunction "PK2(ADC10/PCINT18)_87") (pintype "bidirectional"))
      (node (ref "R24") (pin "1") (pinfunction "1_1") (pintype "passive"))
    )
    (net (code "79") (name "D65{slash}ADC11{slash}HOTEND") (class "Default")
      (node (ref "IC3") (pin "86") (pinfunction "PK3(ADC11/PCINT19)_86") (pintype "bidirectional"))
      (node (ref "R62") (pin "1") (pinfunction "1_1") (pintype "passive"))
    )
    (net (code "80") (name "D66{slash}ADC12{slash}E-FAN") (class "Default")
      (node (ref "IC3") (pin "85") (pinfunction "PK4(ADC12/PCINT20)_85") (pintype "bidirectional"))
      (node (ref "R35") (pin "2") (pinfunction "2_2") (pintype "passive"))
    )
    (net (code "81") (name "D67{slash}ADC13") (class "Default")
      (node (ref "IC3") (pin "84") (pinfunction "PK5(ADC13/PCINT21)_84") (pintype "bidirectional"))
      (node (ref "R28") (pin "2") (pinfunction "2_2") (pintype "passive"))
    )
    (net (code "82") (name "D68{slash}ADC14{slash}TH2_BED") (class "Default")
      (node (ref "BEDTH") (pin "2") (pinfunction "1_2") (pintype "passive"))
      (node (ref "C4") (pin "A") (pinfunction "+_A") (pintype "passive"))
      (node (ref "IC3") (pin "83") (pinfunction "PK6(ADC14/PCINT22)_83") (pintype "bidirectional"))
      (node (ref "R27") (pin "2") (pinfunction "2_2") (pintype "passive"))
    )
    (net (code "83") (name "D69{slash}ADC15{slash}TH1_HOTEND") (class "Default")
      (node (ref "C3") (pin "A") (pinfunction "+_A") (pintype "passive"))
      (node (ref "ETHERM") (pin "2") (pinfunction "1_2") (pintype "passive"))
      (node (ref "IC3") (pin "82") (pinfunction "PK7(ADC15/PCINT23)_82") (pintype "bidirectional"))
      (node (ref "J1") (pin "10") (pinfunction "10_10") (pintype "passive"))
      (node (ref "R26") (pin "2") (pinfunction "2_2") (pintype "passive"))
    )
    (net (code "84") (name "DI") (class "Default")
      (node (ref "IC1") (pin "4") (pinfunction "O_4") (pintype "output"))
      (node (ref "U2") (pin "3") (pinfunction "DI_3") (pintype "bidirectional"))
    )
    (net (code "85") (name "DTR") (class "Default")
      (node (ref "C46") (pin "1") (pinfunction "1_1") (pintype "passive"))
      (node (ref "U6") (pin "2") (pinfunction "DTR_2") (pintype "output"))
    )
    (net (code "86") (name "E-FAN-NEG") (class "Default")
      (node (ref "D13") (pin "A") (pinfunction "A_A") (pintype "passive"))
      (node (ref "J2") (pin "1") (pinfunction "1_1") (pintype "passive"))
      (node (ref "J2") (pin "2") (pinfunction "2_2") (pintype "passive"))
      (node (ref "Q1") (pin "4") (pinfunction "D_4") (pintype "passive"))
      (node (ref "X-END3") (pin "1") (pinfunction "1_1") (pintype "passive"))
    )
    (net (code "87") (name "EMODE0") (class "Default")
      (node (ref "R45") (pin "1") (pinfunction "1_1") (pintype "passive"))
      (node (ref "U$7") (pin "DMODE0") (pinfunction "DMODE0_DMODE0") (pintype "bidirectional"))
    )
    (net (code "88") (name "EMODE1") (class "Default")
      (node (ref "R46") (pin "1") (pinfunction "1_1") (pintype "passive"))
      (node (ref "SJ5") (pin "2") (pinfunction "2_2") (pintype "passive"))
      (node (ref "U$7") (pin "DMODE1") (pinfunction "DMODE1_DMODE1") (pintype "bidirectional"))
    )
    (net (code "89") (name "EMODE2") (class "Default")
      (node (ref "R47") (pin "1") (pinfunction "1_1") (pintype "passive"))
      (node (ref "SJ6") (pin "2") (pinfunction "2_2") (pintype "passive"))
      (node (ref "U$7") (pin "DMODE2") (pinfunction "DMODE2_DMODE2") (pintype "bidirectional"))
    )
    (net (code "90") (name "EOUT-A+") (class "Default")
      (node (ref "D9") (pin "C") (pinfunction "C_C") (pintype "passive"))
      (node (ref "J7") (pin "1") (pinfunction "1_1") (pintype "passive"))
      (node (ref "J7") (pin "2") (pinfunction "2_2") (pintype "passive"))
      (node (ref "U$7") (pin "OUTA+1") (pinfunction "OUTA+1_OUTA+1") (pintype "bidirectional"))
      (node (ref "U$7") (pin "OUTA+2") (pinfunction "OUTA+2_OUTA+2") (pintype "bidirectional"))
    )
    (net (code "91") (name "EOUT-A-") (class "Default")
      (node (ref "D9") (pin "A") (pinfunction "A_A") (pintype "passive"))
      (node (ref "J7") (pin "3") (pinfunction "3_3") (pintype "passive"))
      (node (ref "J7") (pin "4") (pinfunction "4_4") (pintype "passive"))
      (node (ref "U$7") (pin "OUTA-1") (pinfunction "OUTA-1_OUTA-1") (pintype "bidirectional"))
      (node (ref "U$7") (pin "OUTA-2") (pinfunction "OUTA-2_OUTA-2") (pintype "bidirectional"))
    )
    (net (code "92") (name "EOUT-B+") (class "Default")
      (node (ref "D10") (pin "A") (pinfunction "A_A") (pintype "passive"))
      (node (ref "J7") (pin "7") (pinfunction "7_7") (pintype "passive"))
      (node (ref "J7") (pin "8") (pinfunction "8_8") (pintype "passive"))
      (node (ref "U$7") (pin "OUTB+1") (pinfunction "OUTB+1_OUTB+1") (pintype "bidirectional"))
      (node (ref "U$7") (pin "OUTB+2") (pinfunction "OUTB+2_OUTB+2") (pintype "bidirectional"))
    )
    (net (code "93") (name "EOUT-B-") (class "Default")
      (node (ref "D10") (pin "C") (pinfunction "C_C") (pintype "passive"))
      (node (ref "J7") (pin "5") (pinfunction "5_5") (pintype "passive"))
      (node (ref "J7") (pin "6") (pinfunction "6_6") (pintype "passive"))
      (node (ref "U$7") (pin "OUTB-1") (pinfunction "OUTB-1_OUTB-1") (pintype "bidirectional"))
      (node (ref "U$7") (pin "OUTB-2") (pinfunction "OUTB-2_OUTB-2") (pintype "bidirectional"))
    )
    (net (code "94") (name "GATE_CMD") (class "Default")
      (node (ref "IC5") (pin "7") (pinfunction "OUT_7") (pintype "output"))
      (node (ref "T2") (pin "3") (pinfunction "G_3") (pintype "passive"))
    )
    (net (code "95") (name "GND") (class "Default")
      (node (ref "C1") (pin "-") (pinfunction "-_-") (pintype "passive"))
      (node (ref "C10") (pin "2") (pinfunction "2_2") (pintype "passive"))
      (node (ref "C11") (pin "2") (pinfunction "2_2") (pintype "passive"))
      (node (ref "C12") (pin "2") (pinfunction "2_2") (pintype "passive"))
      (node (ref "C13") (pin "2") (pinfunction "2_2") (pintype "passive"))
      (node (ref "C14") (pin "2") (pinfunction "2_2") (pintype "passive"))
      (node (ref "C15") (pin "2") (pinfunction "2_2") (pintype "passive"))
      (node (ref "C16") (pin "2") (pinfunction "2_2") (pintype "passive"))
      (node (ref "C17") (pin "2") (pinfunction "2_2") (pintype "passive"))
      (node (ref "C18") (pin "2") (pinfunction "2_2") (pintype "passive"))
      (node (ref "C19") (pin "2") (pinfunction "2_2") (pintype "passive"))
      (node (ref "C2") (pin "-") (pinfunction "-_-") (pintype "passive"))
      (node (ref "C20") (pin "2") (pinfunction "2_2") (pintype "passive"))
      (node (ref "C21") (pin "2") (pinfunction "2_2") (pintype "passive"))
      (node (ref "C22") (pin "2") (pinfunction "2_2") (pintype "passive"))
      (node (ref "C23") (pin "2") (pinfunction "2_2") (pintype "passive"))
      (node (ref "C24") (pin "2") (pinfunction "2_2") (pintype "passive"))
      (node (ref "C25") (pin "2") (pinfunction "2_2") (pintype "passive"))
      (node (ref "C26") (pin "2") (pinfunction "2_2") (pintype "passive"))
      (node (ref "C27") (pin "2") (pinfunction "2_2") (pintype "passive"))
      (node (ref "C28") (pin "1") (pinfunction "1_1") (pintype "passive"))
      (node (ref "C29") (pin "1") (pinfunction "1_1") (pintype "passive"))
      (node (ref "C30") (pin "1") (pinfunction "1_1") (pintype "passive"))
      (node (ref "C31") (pin "1") (pinfunction "1_1") (pintype "passive"))
      (node (ref "C32") (pin "C") (pinfunction "-_C") (pintype "passive"))
      (node (ref "C33") (pin "2") (pinfunction "2_2") (pintype "passive"))
      (node (ref "C34") (pin "2") (pinfunction "2_2") (pintype "passive"))
      (node (ref "C35") (pin "C") (pinfunction "-_C") (pintype "passive"))
      (node (ref "C36") (pin "1") (pinfunction "1_1") (pintype "passive"))
      (node (ref "C37") (pin "C") (pinfunction "-_C") (pintype "passive"))
      (node (ref "C38") (pin "C") (pinfunction "-_C") (pintype "passive"))
      (node (ref "C39") (pin "C") (pinfunction "-_C") (pintype "passive"))
      (node (ref "C40") (pin "-") (pinfunction "-_-") (pintype "passive"))
      (node (ref "C41") (pin "-") (pinfunction "-_-") (pintype "passive"))
      (node (ref "C42") (pin "-") (pinfunction "-_-") (pintype "passive"))
      (node (ref "C43") (pin "2") (pinfunction "2_2") (pintype "passive"))
      (node (ref "C44") (pin "C") (pinfunction "-_C") (pintype "passive"))
      (node (ref "C45") (pin "2") (pinfunction "2_2") (pintype "passive"))
      (node (ref "C47") (pin "C") (pinfunction "-_C") (pintype "passive"))
      (node (ref "C48") (pin "C") (pinfunction "-_C") (pintype "passive"))
      (node (ref "C49") (pin "2") (pinfunction "2_2") (pintype "passive"))
      (node (ref "C5") (pin "2") (pinfunction "2_2") (pintype "passive"))
      (node (ref "C50") (pin "2") (pinfunction "2_2") (pintype "passive"))
      (node (ref "C51") (pin "C") (pinfunction "-_C") (pintype "passive"))
      (node (ref "C52") (pin "C") (pinfunction "-_C") (pintype "passive"))
      (node (ref "C56") (pin "-") (pinfunction "-_-") (pintype "passive"))
      (node (ref "C6") (pin "2") (pinfunction "2_2") (pintype "passive"))
      (node (ref "C7") (pin "2") (pinfunction "2_2") (pintype "passive"))
      (node (ref "C8") (pin "2") (pinfunction "2_2") (pintype "passive"))
      (node (ref "C9") (pin "2") (pinfunction "2_2") (pintype "passive"))
      (node (ref "D14") (pin "A") (pinfunction "A_A") (pintype "passive"))
      (node (ref "D18") (pin "2") (pinfunction "A_2") (pintype "passive"))
      (node (ref "IC1") (pin "8") (pinfunction "VSS_8") (pintype "power_in"))
      (node (ref "IC2") (pin "1") (pinfunction "ADJ_1") (pintype "input"))
      (node (ref "IC3") (pin "11") (pinfunction "GND_11") (pintype "power_in"))
      (node (ref "IC3") (pin "32") (pinfunction "GND1_32") (pintype "power_in"))
      (node (ref "IC3") (pin "62") (pinfunction "GND2_62") (pintype "power_in"))
      (node (ref "IC3") (pin "81") (pinfunction "GND3_81") (pintype "power_in"))
      (node (ref "IC3") (pin "99") (pinfunction "AGND_99") (pintype "power_in"))
      (node (ref "IC5") (pin "2") (pinfunction "-IN_2") (pintype "input"))
      (node (ref "IC5") (pin "3") (pinfunction "+IN_3") (pintype "input"))
      (node (ref "IC5") (pin "4") (pinfunction "V-_4") (pintype "power_in"))
      (node (ref "IC9") (pin "4") (pinfunction "EN_4") (pintype "bidirectional"))
      (node (ref "IC9") (pin "5") (pinfunction "GND1_5") (pintype "bidirectional"))
      (node (ref "IC9") (pin "6") (pinfunction "GND2_6") (pintype "bidirectional"))
      (node (ref "IC9") (pin "7") (pinfunction "GND3_7") (pintype "bidirectional"))
      (node (ref "IC9") (pin "8") (pinfunction "GND4_8") (pintype "bidirectional"))
      (node (ref "ICSP") (pin "6") (pinfunction "6_6") (pintype "passive"))
      (node (ref "J3") (pin "GND") (pinfunction "GND_GND") (pintype "bidirectional"))
      (node (ref "J3") (pin "GND2") (pinfunction "GND_GND2") (pintype "bidirectional"))
      (node (ref "J6") (pin "10") (pinfunction "10_10") (pintype "passive"))
      (node (ref "J7") (pin "10") (pinfunction "10_10") (pintype "passive"))
      (node (ref "J8") (pin "10") (pinfunction "10_10") (pintype "passive"))
      (node (ref "L") (pin "C") (pinfunction "C_C") (pintype "passive"))
      (node (ref "L3") (pin "2") (pinfunction "2_2") (pintype "passive"))
      (node (ref "MOS2") (pin "3") (pinfunction "S_3") (pintype "passive"))
      (node (ref "ON") (pin "C") (pinfunction "C_C") (pintype "passive"))
      (node (ref "PWRIN") (pin "1") (pinfunction "1_1") (pintype "passive"))
      (node (ref "Q1") (pin "3") (pinfunction "S_3") (pintype "passive"))
      (node (ref "Q2") (pin "3") (pinfunction "S_3") (pintype "passive"))
      (node (ref "Q22") (pin "3") (pinfunction "S_3") (pintype "passive"))
      (node (ref "R1") (pin "1") (pinfunction "1_1") (pintype "passive"))
      (node (ref "R17") (pin "1") (pinfunction "1_1") (pintype "passive"))
      (node (ref "R2") (pin "1") (pinfunction "1_1") (pintype "passive"))
      (node (ref "R25") (pin "1") (pinfunction "1_1") (pintype "passive"))
      (node (ref "R44") (pin "1") (pinfunction "1_1") (pintype "passive"))
      (node (ref "R5") (pin "1") (pinfunction "1_1") (pintype "passive"))
      (node (ref "R53") (pin "1") (pinfunction "1_1") (pintype "passive"))
      (node (ref "R63") (pin "1") (pinfunction "1_1") (pintype "passive"))
      (node (ref "R67") (pin "1") (pinfunction "1_1") (pintype "passive"))
      (node (ref "R7") (pin "1") (pinfunction "1_1") (pintype "passive"))
      (node (ref "R70") (pin "1") (pinfunction "1_1") (pintype "passive"))
      (node (ref "R71") (pin "1") (pinfunction "1_1") (pintype "passive"))
      (node (ref "RESET") (pin "1") (pinfunction "1_1") (pintype "passive"))
      (node (ref "RESET") (pin "2") (pinfunction "2_2") (pintype "passive"))
      (node (ref "SJ1") (pin "1") (pinfunction "1_1") (pintype "passive"))
      (node (ref "SJ2") (pin "1") (pinfunction "1_1") (pintype "passive"))
      (node (ref "SJ3") (pin "1") (pinfunction "1_1") (pintype "passive"))
      (node (ref "SJ4") (pin "1") (pinfunction "1_1") (pintype "passive"))
      (node (ref "SJ5") (pin "1") (pinfunction "1_1") (pintype "passive"))
      (node (ref "SJ6") (pin "1") (pinfunction "1_1") (pintype "passive"))
      (node (ref "SJ7") (pin "1") (pinfunction "1_1") (pintype "passive"))
      (node (ref "SJ8") (pin "1") (pinfunction "1_1") (pintype "passive"))
      (node (ref "U$1") (pin "GND") (pinfunction "GND1_GND") (pintype "bidirectional"))
      (node (ref "U$1") (pin "GND-PAD") (pinfunction "GNDPAD_GND-PAD") (pintype "bidirectional"))
      (node (ref "U$1") (pin "GND2") (pinfunction "GND2_GND2") (pintype "bidirectional"))
      (node (ref "U$1") (pin "GND3") (pinfunction "GND3_GND3") (pintype "bidirectional"))
      (node (ref "U$1") (pin "GND4") (pinfunction "GND4_GND4") (pintype "bidirectional"))
      (node (ref "U$1") (pin "GND5") (pinfunction "GND5_GND5") (pintype "bidirectional"))
      (node (ref "U$1") (pin "GND6") (pinfunction "GND6_GND6") (pintype "bidirectional"))
      (node (ref "U$17") (pin "GND") (pinfunction "GND1_GND") (pintype "bidirectional"))
      (node (ref "U$17") (pin "GND-PAD") (pinfunction "GNDPAD_GND-PAD") (pintype "bidirectional"))
      (node (ref "U$17") (pin "GND2") (pinfunction "GND2_GND2") (pintype "bidirectional"))
      (node (ref "U$17") (pin "GND3") (pinfunction "GND3_GND3") (pintype "bidirectional"))
      (node (ref "U$17") (pin "GND4") (pinfunction "GND4_GND4") (pintype "bidirectional"))
      (node (ref "U$17") (pin "GND5") (pinfunction "GND5_GND5") (pintype "bidirectional"))
      (node (ref "U$17") (pin "GND6") (pinfunction "GND6_GND6") (pintype "bidirectional"))
      (node (ref "U$2") (pin "GND") (pinfunction "GND1_GND") (pintype "bidirectional"))
      (node (ref "U$2") (pin "GND-PAD") (pinfunction "GNDPAD_GND-PAD") (pintype "bidirectional"))
      (node (ref "U$2") (pin "GND2") (pinfunction "GND2_GND2") (pintype "bidirectional"))
      (node (ref "U$2") (pin "GND3") (pinfunction "GND3_GND3") (pintype "bidirectional"))
      (node (ref "U$2") (pin "GND4") (pinfunction "GND4_GND4") (pintype "bidirectional"))
      (node (ref "U$2") (pin "GND5") (pinfunction "GND5_GND5") (pintype "bidirectional"))
      (node (ref "U$2") (pin "GND6") (pinfunction "GND6_GND6") (pintype "bidirectional"))
      (node (ref "U$7") (pin "GND") (pinfunction "GND1_GND") (pintype "bidirectional"))
      (node (ref "U$7") (pin "GND-PAD") (pinfunction "GNDPAD_GND-PAD") (pintype "bidirectional"))
      (node (ref "U$7") (pin "GND2") (pinfunction "GND2_GND2") (pintype "bidirectional"))
      (node (ref "U$7") (pin "GND3") (pinfunction "GND3_GND3") (pintype "bidirectional"))
      (node (ref "U$7") (pin "GND4") (pinfunction "GND4_GND4") (pintype "bidirectional"))
      (node (ref "U$7") (pin "GND5") (pinfunction "GND5_GND5") (pintype "bidirectional"))
      (node (ref "U$7") (pin "GND6") (pinfunction "GND6_GND6") (pintype "bidirectional"))
      (node (ref "U1") (pin "11") (pinfunction "11_11") (pintype "passive"))
      (node (ref "U1") (pin "13") (pinfunction "13_13") (pintype "passive"))
      (node (ref "U1") (pin "15") (pinfunction "15_15") (pintype "passive"))
      (node (ref "U1") (pin "9") (pinfunction "9_9") (pintype "passive"))
      (node (ref "U2") (pin "6") (pinfunction "GND_6") (pintype "bidirectional"))
      (node (ref "U2") (pin "GND1") (pinfunction "SHIELD_GND1") (pintype "bidirectional"))
      (node (ref "U2") (pin "GND2") (pinfunction "SHIELD_GND2") (pintype "bidirectional"))
      (node (ref "U6") (pin "18") (pinfunction "GND18_18") (pintype "power_in"))
      (node (ref "U6") (pin "21") (pinfunction "GND21_21") (pintype "power_in"))
      (node (ref "U6") (pin "25") (pinfunction "AGND_25") (pintype "power_in"))
      (node (ref "U6") (pin "26") (pinfunction "TEST_26") (pintype "input"))
      (node (ref "U6") (pin "7") (pinfunction "GND7_7") (pintype "power_in"))
      (node (ref "Z-CONN1") (pin "10") (pinfunction "10_10") (pintype "passive"))
    )
    (net (code "96") (name "HOTEND-NEG1") (class "Default")
      (node (ref "D3") (pin "A") (pinfunction "A_A") (pintype "passive"))
      (node (ref "J1") (pin "1") (pinfunction "1_1") (pintype "passive"))
      (node (ref "J1") (pin "2") (pinfunction "2_2") (pintype "passive"))
      (node (ref "J1") (pin "3") (pinfunction "3_3") (pintype "passive"))
      (node (ref "J1") (pin "4") (pinfunction "4_4") (pintype "passive"))
      (node (ref "Q2") (pin "4") (pinfunction "D_4") (pintype "passive"))
      (node (ref "X-END1") (pin "1") (pinfunction "1_1") (pintype "passive"))
    )
    (net (code "97") (name "M8RXD") (class "Default")
      (node (ref "R68") (pin "1") (pinfunction "1_1") (pintype "passive"))
      (node (ref "U6") (pin "1") (pinfunction "TXD_1") (pintype "output"))
    )
    (net (code "98") (name "M8TXD") (class "Default")
      (node (ref "R69") (pin "1") (pinfunction "1_1") (pintype "passive"))
      (node (ref "U6") (pin "5") (pinfunction "RXD_5") (pintype "input"))
    )
    (net (code "99") (name "Net-(C11-Pad1)") (class "Default")
      (node (ref "C11") (pin "1") (pinfunction "1_1") (pintype "passive"))
      (node (ref "R3") (pin "S") (pinfunction "S_S") (pintype "passive"))
      (node (ref "U$17") (pin "VREFA") (pinfunction "VREFA_VREFA") (pintype "bidirectional"))
      (node (ref "U$17") (pin "VREFB") (pinfunction "VREFB_VREFB") (pintype "bidirectional"))
    )
    (net (code "100") (name "Net-(C12-Pad1)") (class "Default")
      (node (ref "C12") (pin "1") (pinfunction "1_1") (pintype "passive"))
      (node (ref "R12") (pin "1") (pinfunction "1_1") (pintype "passive"))
      (node (ref "U$17") (pin "OSCM") (pinfunction "OSCM_OSCM") (pintype "bidirectional"))
    )
    (net (code "101") (name "Net-(C17-Pad1)") (class "Default")
      (node (ref "C17") (pin "1") (pinfunction "1_1") (pintype "passive"))
      (node (ref "R4") (pin "S") (pinfunction "S_S") (pintype "passive"))
      (node (ref "U$1") (pin "VREFA") (pinfunction "VREFA_VREFA") (pintype "bidirectional"))
      (node (ref "U$1") (pin "VREFB") (pinfunction "VREFB_VREFB") (pintype "bidirectional"))
    )
    (net (code "102") (name "Net-(C18-Pad1)") (class "Default")
      (node (ref "C18") (pin "1") (pinfunction "1_1") (pintype "passive"))
      (node (ref "R32") (pin "1") (pinfunction "1_1") (pintype "passive"))
      (node (ref "U$1") (pin "OSCM") (pinfunction "OSCM_OSCM") (pintype "bidirectional"))
    )
    (net (code "103") (name "Net-(C22-Pad1)") (class "Default")
      (node (ref "C22") (pin "1") (pinfunction "1_1") (pintype "passive"))
      (node (ref "R20") (pin "S") (pinfunction "S_S") (pintype "passive"))
      (node (ref "U$2") (pin "VREFA") (pinfunction "VREFA_VREFA") (pintype "bidirectional"))
      (node (ref "U$2") (pin "VREFB") (pinfunction "VREFB_VREFB") (pintype "bidirectional"))
    )
    (net (code "104") (name "Net-(C23-Pad1)") (class "Default")
      (node (ref "C23") (pin "1") (pinfunction "1_1") (pintype "passive"))
      (node (ref "R41") (pin "1") (pinfunction "1_1") (pintype "passive"))
      (node (ref "U$2") (pin "OSCM") (pinfunction "OSCM_OSCM") (pintype "bidirectional"))
    )
    (net (code "105") (name "Net-(C27-Pad1)") (class "Default")
      (node (ref "C27") (pin "1") (pinfunction "1_1") (pintype "passive"))
      (node (ref "R21") (pin "S") (pinfunction "S_S") (pintype "passive"))
      (node (ref "U$7") (pin "VREFA") (pinfunction "VREFA_VREFA") (pintype "bidirectional"))
      (node (ref "U$7") (pin "VREFB") (pinfunction "VREFB_VREFB") (pintype "bidirectional"))
    )
    (net (code "106") (name "Net-(C33-Pad1)") (class "Default")
      (node (ref "C33") (pin "1") (pinfunction "1_1") (pintype "passive"))
      (node (ref "R50") (pin "1") (pinfunction "1_1") (pintype "passive"))
      (node (ref "U$7") (pin "OSCM") (pinfunction "OSCM_OSCM") (pintype "bidirectional"))
    )
    (net (code "107") (name "Net-(D11-C)") (class "Default")
      (node (ref "D11") (pin "1") (pinfunction "C_1") (pintype "passive"))
      (node (ref "IC9") (pin "1") (pinfunction "IN_1") (pintype "bidirectional"))
    )
    (net (code "108") (name "Net-(D15-C)") (class "Default")
      (node (ref "D15") (pin "1") (pinfunction "C_1") (pintype "passive"))
      (node (ref "T2") (pin "1") (pinfunction "D_1") (pintype "passive"))
    )
    (net (code "109") (name "Net-(D16-PadA)") (class "Default")
      (node (ref "D16") (pin "A") (pinfunction "A_A") (pintype "passive"))
      (node (ref "U1") (pin "2") (pinfunction "2_2") (pintype "passive"))
    )
    (net (code "110") (name "Net-(D17-PadA)") (class "Default")
      (node (ref "D17") (pin "A") (pinfunction "A_A") (pintype "passive"))
      (node (ref "U1") (pin "4") (pinfunction "4_4") (pintype "passive"))
    )
    (net (code "111") (name "Net-(D18-C)") (class "Default")
      (node (ref "D18") (pin "1") (pinfunction "C_1") (pintype "passive"))
      (node (ref "IC9") (pin "2") (pinfunction "OUT_2") (pintype "bidirectional"))
      (node (ref "L2") (pin "2") (pinfunction "2_2") (pintype "passive"))
    )
    (net (code "112") (name "Net-(D19-PadA)") (class "Default")
      (node (ref "D19") (pin "A") (pinfunction "A_A") (pintype "passive"))
      (node (ref "U1") (pin "6") (pinfunction "6_6") (pintype "passive"))
    )
    (net (code "113") (name "Net-(D20-PadA)") (class "Default")
      (node (ref "D20") (pin "A") (pinfunction "A_A") (pintype "passive"))
      (node (ref "U1") (pin "8") (pinfunction "8_8") (pintype "passive"))
    )
    (net (code "114") (name "Net-(D21-C1)") (class "Default")
      (node (ref "D21") (pin "3") (pinfunction "C1_3") (pintype "bidirectional"))
      (node (ref "R73") (pin "2") (pinfunction "2_2") (pintype "passive"))
    )
    (net (code "115") (name "Net-(D21-C2)") (class "Default")
      (node (ref "D21") (pin "4") (pinfunction "C2_4") (pintype "bidirectional"))
      (node (ref "R72") (pin "2") (pinfunction "2_2") (pintype "passive"))
    )
    (net (code "116") (name "Net-(J3-CC1)") (class "Default")
      (node (ref "J3") (pin "A5") (pinfunction "CC1_A5") (pintype "bidirectional"))
      (node (ref "R71") (pin "2") (pinfunction "2_2") (pintype "passive"))
    )
    (net (code "117") (name "Net-(J3-CC2)") (class "Default")
      (node (ref "J3") (pin "B5") (pinfunction "CC2_B5") (pintype "bidirectional"))
      (node (ref "R70") (pin "2") (pinfunction "2_2") (pintype "passive"))
    )
    (net (code "118") (name "Net-(L-PadA)") (class "Default")
      (node (ref "L") (pin "A") (pinfunction "A_A") (pintype "passive"))
      (node (ref "R55") (pin "2") (pinfunction "2_2") (pintype "passive"))
    )
    (net (code "119") (name "Net-(LED6-C)") (class "Default")
      (node (ref "LED6") (pin "K") (pinfunction "C_K") (pintype "passive"))
      (node (ref "R2") (pin "2") (pinfunction "2_2") (pintype "passive"))
    )
    (net (code "120") (name "Net-(MOS2-G)") (class "Default")
      (node (ref "MOS2") (pin "1") (pinfunction "G_1") (pintype "passive"))
      (node (ref "R24") (pin "2") (pinfunction "2_2") (pintype "passive"))
      (node (ref "R25") (pin "2") (pinfunction "2_2") (pintype "passive"))
    )
    (net (code "121") (name "Net-(ON-PadA)") (class "Default")
      (node (ref "ON") (pin "A") (pinfunction "A_A") (pintype "passive"))
      (node (ref "R60") (pin "2") (pinfunction "2_2") (pintype "passive"))
    )
    (net (code "122") (name "Net-(Q1-G)") (class "Default")
      (node (ref "Q1") (pin "1") (pinfunction "G_1") (pintype "passive"))
      (node (ref "R35") (pin "1") (pinfunction "1_1") (pintype "passive"))
      (node (ref "R53") (pin "2") (pinfunction "2_2") (pintype "passive"))
    )
    (net (code "123") (name "Net-(Q2-G)") (class "Default")
      (node (ref "Q2") (pin "1") (pinfunction "G_1") (pintype "passive"))
      (node (ref "R62") (pin "2") (pinfunction "2_2") (pintype "passive"))
      (node (ref "R63") (pin "2") (pinfunction "2_2") (pintype "passive"))
    )
    (net (code "124") (name "Net-(Q22-G)") (class "Default")
      (node (ref "Q22") (pin "1") (pinfunction "G_1") (pintype "passive"))
      (node (ref "R28") (pin "1") (pinfunction "1_1") (pintype "passive"))
      (node (ref "R44") (pin "2") (pinfunction "2_2") (pintype "passive"))
    )
    (net (code "125") (name "Net-(R1-Pad2)") (class "Default")
      (node (ref "R1") (pin "2") (pinfunction "2_2") (pintype "passive"))
      (node (ref "R4") (pin "A") (pinfunction "A_A") (pintype "passive"))
    )
    (net (code "126") (name "Net-(R10-Pad1)") (class "Default")
      (node (ref "R10") (pin "1") (pinfunction "1_1") (pintype "passive"))
      (node (ref "U$17") (pin "RSB1") (pinfunction "RSB1_RSB1") (pintype "bidirectional"))
      (node (ref "U$17") (pin "RSB2") (pinfunction "RSB2_RSB2") (pintype "bidirectional"))
    )
    (net (code "127") (name "Net-(R14-Pad1)") (class "Default")
      (node (ref "R14") (pin "1") (pinfunction "1_1") (pintype "passive"))
      (node (ref "U$17") (pin "MO") (pinfunction "MO_MO") (pintype "bidirectional"))
    )
    (net (code "128") (name "Net-(R17-Pad2)") (class "Default")
      (node (ref "R17") (pin "2") (pinfunction "2_2") (pintype "passive"))
      (node (ref "R3") (pin "A") (pinfunction "A_A") (pintype "passive"))
    )
    (net (code "129") (name "Net-(R18-Pad1)") (class "Default")
      (node (ref "R18") (pin "1") (pinfunction "1_1") (pintype "passive"))
      (node (ref "R3") (pin "E") (pinfunction "E_E") (pintype "passive"))
    )
    (net (code "130") (name "Net-(R19-Pad1)") (class "Default")
      (node (ref "R19") (pin "1") (pinfunction "1_1") (pintype "passive"))
      (node (ref "R4") (pin "E") (pinfunction "E_E") (pintype "passive"))
    )
    (net (code "131") (name "Net-(R20-PadA)") (class "Default")
      (node (ref "R20") (pin "A") (pinfunction "A_A") (pintype "passive"))
      (node (ref "R5") (pin "2") (pinfunction "2_2") (pintype "passive"))
    )
    (net (code "132") (name "Net-(R20-PadE)") (class "Default")
      (node (ref "R20") (pin "E") (pinfunction "E_E") (pintype "passive"))
      (node (ref "R22") (pin "1") (pinfunction "1_1") (pintype "passive"))
    )
    (net (code "133") (name "Net-(R21-PadA)") (class "Default")
      (node (ref "R21") (pin "A") (pinfunction "A_A") (pintype "passive"))
      (node (ref "R7") (pin "2") (pinfunction "2_2") (pintype "passive"))
    )
    (net (code "134") (name "Net-(R21-PadE)") (class "Default")
      (node (ref "R21") (pin "E") (pinfunction "E_E") (pintype "passive"))
      (node (ref "R23") (pin "1") (pinfunction "1_1") (pintype "passive"))
    )
    (net (code "135") (name "Net-(R30-Pad1)") (class "Default")
      (node (ref "R30") (pin "1") (pinfunction "1_1") (pintype "passive"))
      (node (ref "U$1") (pin "RSB1") (pinfunction "RSB1_RSB1") (pintype "bidirectional"))
      (node (ref "U$1") (pin "RSB2") (pinfunction "RSB2_RSB2") (pintype "bidirectional"))
    )
    (net (code "136") (name "Net-(R34-Pad1)") (class "Default")
      (node (ref "R34") (pin "1") (pinfunction "1_1") (pintype "passive"))
      (node (ref "U$1") (pin "MO") (pinfunction "MO_MO") (pintype "bidirectional"))
    )
    (net (code "137") (name "Net-(R43-Pad1)") (class "Default")
      (node (ref "R43") (pin "1") (pinfunction "1_1") (pintype "passive"))
      (node (ref "U$2") (pin "MO") (pinfunction "MO_MO") (pintype "bidirectional"))
    )
    (net (code "138") (name "Net-(R52-Pad1)") (class "Default")
      (node (ref "R52") (pin "1") (pinfunction "1_1") (pintype "passive"))
      (node (ref "U$7") (pin "MO") (pinfunction "MO_MO") (pintype "bidirectional"))
    )
    (net (code "139") (name "Net-(R74-Pad2)") (class "Default")
      (node (ref "R74") (pin "2") (pinfunction "2_2") (pintype "passive"))
      (node (ref "U1") (pin "1") (pinfunction "1_1") (pintype "passive"))
    )
    (net (code "140") (name "Net-(R75-Pad2)") (class "Default")
      (node (ref "R75") (pin "2") (pinfunction "2_2") (pintype "passive"))
      (node (ref "U1") (pin "3") (pinfunction "3_3") (pintype "passive"))
    )
    (net (code "141") (name "Net-(R76-Pad2)") (class "Default")
      (node (ref "R76") (pin "2") (pinfunction "2_2") (pintype "passive"))
      (node (ref "U1") (pin "5") (pinfunction "5_5") (pintype "passive"))
    )
    (net (code "142") (name "Net-(R77-Pad2)") (class "Default")
      (node (ref "R77") (pin "2") (pinfunction "2_2") (pintype "passive"))
      (node (ref "U1") (pin "7") (pinfunction "7_7") (pintype "passive"))
    )
    (net (code "143") (name "Net-(U$1-RSA1)") (class "Default")
      (node (ref "R31") (pin "1") (pinfunction "1_1") (pintype "passive"))
      (node (ref "U$1") (pin "RSA") (pinfunction "RSA1_RSA") (pintype "bidirectional"))
      (node (ref "U$1") (pin "RSA2") (pinfunction "RSA2_RSA2") (pintype "bidirectional"))
    )
    (net (code "144") (name "Net-(U$17-RSA1)") (class "Default")
      (node (ref "R11") (pin "1") (pinfunction "1_1") (pintype "passive"))
      (node (ref "U$17") (pin "RSA") (pinfunction "RSA1_RSA") (pintype "bidirectional"))
      (node (ref "U$17") (pin "RSA2") (pinfunction "RSA2_RSA2") (pintype "bidirectional"))
    )
    (net (code "145") (name "PART-FAN-NEG") (class "Default")
      (node (ref "D12") (pin "A") (pinfunction "A_A") (pintype "passive"))
      (node (ref "J2") (pin "5") (pinfunction "5_5") (pintype "passive"))
      (node (ref "J2") (pin "6") (pinfunction "6_6") (pintype "passive"))
      (node (ref "Q22") (pin "4") (pinfunction "D_4") (pintype "passive"))
      (node (ref "X-END2") (pin "1") (pinfunction "1_1") (pintype "passive"))
    )
    (net (code "146") (name "PH3") (class "Default")
      (node (ref "IC3") (pin "15") (pinfunction "PH3(OC4A)_15") (pintype "bidirectional"))
    )
    (net (code "147") (name "PH4") (class "Default")
      (node (ref "IC3") (pin "16") (pinfunction "PH4(OC4B)_16") (pintype "bidirectional"))
    )
    (net (code "148") (name "RESET") (class "Default")
      (node (ref "C14") (pin "1") (pinfunction "1_1") (pintype "passive"))
      (node (ref "C46") (pin "2") (pinfunction "2_2") (pintype "passive"))
      (node (ref "IC3") (pin "30") (pinfunction "RESET_30") (pintype "input"))
      (node (ref "ICSP") (pin "5") (pinfunction "5_5") (pintype "passive"))
      (node (ref "R61") (pin "1") (pinfunction "1_1") (pintype "passive"))
      (node (ref "RESET") (pin "3") (pinfunction "3_3") (pintype "passive"))
      (node (ref "RESET") (pin "4") (pinfunction "4_4") (pintype "passive"))
    )
    (net (code "149") (name "RTS") (class "Default")
      (node (ref "U6") (pin "3") (pinfunction "RTS_3") (pintype "output"))
    )
    (net (code "150") (name "RXLED") (class "Default")
      (node (ref "R72") (pin "1") (pinfunction "1_1") (pintype "passive"))
      (node (ref "U6") (pin "22") (pinfunction "RXLED_22") (pintype "input"))
    )
    (net (code "151") (name "SC") (class "Default")
      (node (ref "IC1") (pin "6") (pinfunction "O_6") (pintype "output"))
      (node (ref "U2") (pin "5") (pinfunction "SCK_5") (pintype "bidirectional"))
    )
    (net (code "152") (name "SHLD") (class "Default")
      (node (ref "J3") (pin "SHLD1") (pinfunction "SHLD_SHLD1") (pintype "bidirectional"))
      (node (ref "J3") (pin "SHLD2") (pinfunction "SHLD_SHLD2") (pintype "bidirectional"))
      (node (ref "J3") (pin "SHLD3") (pinfunction "SHLD_SHLD3") (pintype "bidirectional"))
      (node (ref "J3") (pin "SHLD4") (pinfunction "SHLD_SHLD4") (pintype "bidirectional"))
      (node (ref "J3") (pin "SHLD5") (pinfunction "SHLD_SHLD5") (pintype "bidirectional"))
      (node (ref "J3") (pin "SHLD6") (pinfunction "SHLD_SHLD6") (pintype "bidirectional"))
      (node (ref "J3") (pin "SHLD7") (pinfunction "SHLD_SHLD7") (pintype "bidirectional"))
      (node (ref "J3") (pin "SHLD8") (pinfunction "SHLD_SHLD8") (pintype "bidirectional"))
    )
    (net (code "153") (name "SPARE1") (class "Default")
      (node (ref "J2") (pin "10") (pinfunction "10_10") (pintype "passive"))
    )
    (net (code "154") (name "SPARE2") (class "Default")
      (node (ref "J2") (pin "9") (pinfunction "9_9") (pintype "passive"))
    )
    (net (code "155") (name "TXLED") (class "Default")
      (node (ref "R73") (pin "1") (pinfunction "1_1") (pintype "passive"))
      (node (ref "U6") (pin "23") (pinfunction "TXLED_23") (pintype "input"))
    )
    (net (code "156") (name "V+PSU") (class "Default")
      (node (ref "PWRIN") (pin "2") (pinfunction "1_2") (pintype "passive"))
      (node (ref "U$4") (pin "TERM1.1") (pinfunction "P$1_TERM1.1") (pintype "bidirectional"))
      (node (ref "U$4") (pin "TERM1.2") (pinfunction "P$1_TERM1.2") (pintype "bidirectional"))
    )
    (net (code "157") (name "VM") (class "Default")
      (node (ref "BED") (pin "2") (pinfunction "1_2") (pintype "passive"))
      (node (ref "C1") (pin "+") (pinfunction "+_+") (pintype "passive"))
      (node (ref "C10") (pin "1") (pinfunction "1_1") (pintype "passive"))
      (node (ref "C16") (pin "1") (pinfunction "1_1") (pintype "passive"))
      (node (ref "C2") (pin "+") (pinfunction "+_+") (pintype "passive"))
      (node (ref "C21") (pin "1") (pinfunction "1_1") (pintype "passive"))
      (node (ref "C26") (pin "1") (pinfunction "1_1") (pintype "passive"))
      (node (ref "C32") (pin "A") (pinfunction "+_A") (pintype "passive"))
      (node (ref "C35") (pin "A") (pinfunction "+_A") (pintype "passive"))
      (node (ref "C37") (pin "A") (pinfunction "+_A") (pintype "passive"))
      (node (ref "C38") (pin "A") (pinfunction "+_A") (pintype "passive"))
      (node (ref "C39") (pin "A") (pinfunction "+_A") (pintype "passive"))
      (node (ref "C40") (pin "+") (pinfunction "+_+") (pintype "passive"))
      (node (ref "C41") (pin "+") (pinfunction "+_+") (pintype "passive"))
      (node (ref "C42") (pin "+") (pinfunction "+_+") (pintype "passive"))
      (node (ref "C48") (pin "A") (pinfunction "+_A") (pintype "passive"))
      (node (ref "D11") (pin "2") (pinfunction "A_2") (pintype "passive"))
      (node (ref "D12") (pin "C") (pinfunction "C_C") (pintype "passive"))
      (node (ref "D13") (pin "C") (pinfunction "C_C") (pintype "passive"))
      (node (ref "D14") (pin "C") (pinfunction "C_C") (pintype "passive"))
      (node (ref "D2") (pin "C") (pinfunction "C_C") (pintype "passive"))
      (node (ref "D3") (pin "C") (pinfunction "C_C") (pintype "passive"))
      (node (ref "J1") (pin "5") (pinfunction "5_5") (pintype "passive"))
      (node (ref "J1") (pin "6") (pinfunction "6_6") (pintype "passive"))
      (node (ref "J1") (pin "7") (pinfunction "7_7") (pintype "passive"))
      (node (ref "J1") (pin "8") (pinfunction "8_8") (pintype "passive"))
      (node (ref "J2") (pin "3") (pinfunction "3_3") (pintype "passive"))
      (node (ref "J2") (pin "4") (pinfunction "4_4") (pintype "passive"))
      (node (ref "J2") (pin "7") (pinfunction "7_7") (pintype "passive"))
      (node (ref "J2") (pin "8") (pinfunction "8_8") (pintype "passive"))
      (node (ref "LED6") (pin "A") (pinfunction "A_A") (pintype "passive"))
      (node (ref "R10") (pin "2") (pinfunction "2_2") (pintype "passive"))
      (node (ref "R11") (pin "2") (pinfunction "2_2") (pintype "passive"))
      (node (ref "R30") (pin "2") (pinfunction "2_2") (pintype "passive"))
      (node (ref "R31") (pin "2") (pinfunction "2_2") (pintype "passive"))
      (node (ref "R39") (pin "2") (pinfunction "2_2") (pintype "passive"))
      (node (ref "R40") (pin "2") (pinfunction "2_2") (pintype "passive"))
      (node (ref "R48") (pin "2") (pinfunction "2_2") (pintype "passive"))
      (node (ref "R49") (pin "2") (pinfunction "2_2") (pintype "passive"))
      (node (ref "U$1") (pin "VM") (pinfunction "VM_VM") (pintype "bidirectional"))
      (node (ref "U$17") (pin "VM") (pinfunction "VM_VM") (pintype "bidirectional"))
      (node (ref "U$2") (pin "VM") (pinfunction "VM_VM") (pintype "bidirectional"))
      (node (ref "U$4") (pin "TERM2.1") (pinfunction "P$2_TERM2.1") (pintype "bidirectional"))
      (node (ref "U$4") (pin "TERM2.2") (pinfunction "P$2_TERM2.2") (pintype "bidirectional"))
      (node (ref "U$7") (pin "VM") (pinfunction "VM_VM") (pintype "bidirectional"))
      (node (ref "X-END1") (pin "2") (pinfunction "1_2") (pintype "passive"))
      (node (ref "X-END2") (pin "2") (pinfunction "1_2") (pintype "passive"))
      (node (ref "X-END3") (pin "2") (pinfunction "1_2") (pintype "passive"))
    )
    (net (code "158") (name "VM_L2") (class "Default")
      (node (ref "R66") (pin "2") (pinfunction "2_2") (pintype "passive"))
    )
    (net (code "159") (name "V_USB") (class "Default")
      (node (ref "C43") (pin "1") (pinfunction "1_1") (pintype "passive"))
      (node (ref "C44") (pin "A") (pinfunction "+_A") (pintype "passive"))
      (node (ref "D15") (pin "2") (pinfunction "A_2") (pintype "passive"))
      (node (ref "D21") (pin "1") (pinfunction "A1_1") (pintype "bidirectional"))
      (node (ref "D21") (pin "2") (pinfunction "A2_2") (pintype "bidirectional"))
      (node (ref "J3") (pin "VBUS1") (pinfunction "VBUS_VBUS1") (pintype "bidirectional"))
      (node (ref "J3") (pin "VBUS2") (pinfunction "VBUS_VBUS2") (pintype "bidirectional"))
      (node (ref "JP5") (pin "1") (pinfunction "1_1") (pintype "passive"))
      (node (ref "U6") (pin "20") (pinfunction "VCC_20") (pintype "power_in"))
      (node (ref "U6") (pin "4") (pinfunction "VCCIO_4") (pintype "power_in"))
    )
    (net (code "160") (name "XFAULT") (class "Default")
      (node (ref "LED1") (pin "A") (pinfunction "A_A") (pintype "passive"))
      (node (ref "R56") (pin "1") (pinfunction "1_1") (pintype "passive"))
    )
    (net (code "161") (name "XLO") (class "Default")
      (node (ref "R13") (pin "1") (pinfunction "1_1") (pintype "passive"))
      (node (ref "R56") (pin "2") (pinfunction "2_2") (pintype "passive"))
      (node (ref "U$17") (pin "LO") (pinfunction "LO_LO") (pintype "bidirectional"))
    )
    (net (code "162") (name "XMODE0") (class "Default")
      (node (ref "R6") (pin "1") (pinfunction "1_1") (pintype "passive"))
      (node (ref "U$17") (pin "DMODE0") (pinfunction "DMODE0_DMODE0") (pintype "bidirectional"))
    )
    (net (code "163") (name "XMODE1") (class "Default")
      (node (ref "R8") (pin "1") (pinfunction "1_1") (pintype "passive"))
      (node (ref "SJ1") (pin "2") (pinfunction "2_2") (pintype "passive"))
      (node (ref "U$17") (pin "DMODE1") (pinfunction "DMODE1_DMODE1") (pintype "bidirectional"))
    )
    (net (code "164") (name "XMODE2") (class "Default")
      (node (ref "R9") (pin "1") (pinfunction "1_1") (pintype "passive"))
      (node (ref "SJ2") (pin "2") (pinfunction "2_2") (pintype "passive"))
      (node (ref "U$17") (pin "DMODE2") (pinfunction "DMODE2_DMODE2") (pintype "bidirectional"))
    )
    (net (code "165") (name "XOUT-A+") (class "Default")
      (node (ref "D1") (pin "C") (pinfunction "C_C") (pintype "passive"))
      (node (ref "U$17") (pin "OUTA+1") (pinfunction "OUTA+1_OUTA+1") (pintype "bidirectional"))
      (node (ref "U$17") (pin "OUTA+2") (pinfunction "OUTA+2_OUTA+2") (pintype "bidirectional"))
      (node (ref "Z-CONN1") (pin "1") (pinfunction "1_1") (pintype "passive"))
      (node (ref "Z-CONN1") (pin "2") (pinfunction "2_2") (pintype "passive"))
    )
    (net (code "166") (name "XOUT-A-") (class "Default")
      (node (ref "D1") (pin "A") (pinfunction "A_A") (pintype "passive"))
      (node (ref "U$17") (pin "OUTA-1") (pinfunction "OUTA-1_OUTA-1") (pintype "bidirectional"))
      (node (ref "U$17") (pin "OUTA-2") (pinfunction "OUTA-2_OUTA-2") (pintype "bidirectional"))
      (node (ref "Z-CONN1") (pin "3") (pinfunction "3_3") (pintype "passive"))
      (node (ref "Z-CONN1") (pin "4") (pinfunction "4_4") (pintype "passive"))
    )
    (net (code "167") (name "XOUT-B+") (class "Default")
      (node (ref "D4") (pin "A") (pinfunction "A_A") (pintype "passive"))
      (node (ref "U$17") (pin "OUTB+1") (pinfunction "OUTB+1_OUTB+1") (pintype "bidirectional"))
      (node (ref "U$17") (pin "OUTB+2") (pinfunction "OUTB+2_OUTB+2") (pintype "bidirectional"))
      (node (ref "Z-CONN1") (pin "7") (pinfunction "7_7") (pintype "passive"))
      (node (ref "Z-CONN1") (pin "8") (pinfunction "8_8") (pintype "passive"))
    )
    (net (code "168") (name "XOUT-B-") (class "Default")
      (node (ref "D4") (pin "C") (pinfunction "C_C") (pintype "passive"))
      (node (ref "U$17") (pin "OUTB-1") (pinfunction "OUTB-1_OUTB-1") (pintype "bidirectional"))
      (node (ref "U$17") (pin "OUTB-2") (pinfunction "OUTB-2_OUTB-2") (pintype "bidirectional"))
      (node (ref "Z-CONN1") (pin "5") (pinfunction "5_5") (pintype "passive"))
      (node (ref "Z-CONN1") (pin "6") (pinfunction "6_6") (pintype "passive"))
    )
    (net (code "169") (name "XTAL1") (class "Default")
      (node (ref "C31") (pin "2") (pinfunction "2_2") (pintype "passive"))
      (node (ref "Q3") (pin "2") (pinfunction "2_2") (pintype "passive"))
      (node (ref "R54") (pin "2") (pinfunction "2_2") (pintype "passive"))
    )
    (net (code "170") (name "XTAL1R") (class "Default")
      (node (ref "IC3") (pin "34") (pinfunction "XTAL1_34") (pintype "input"))
      (node (ref "R54") (pin "1") (pinfunction "1_1") (pintype "passive"))
    )
    (net (code "171") (name "XTAL2") (class "Default")
      (node (ref "C36") (pin "2") (pinfunction "2_2") (pintype "passive"))
      (node (ref "IC3") (pin "33") (pinfunction "XTAL2_33") (pintype "output"))
      (node (ref "Q3") (pin "1") (pinfunction "1_1") (pintype "passive"))
    )
    (net (code "172") (name "XVCCINT") (class "Default")
      (node (ref "C13") (pin "1") (pinfunction "1_1") (pintype "passive"))
      (node (ref "U$17") (pin "VCC") (pinfunction "VCC_VCC") (pintype "bidirectional"))
    )
    (net (code "173") (name "Y2FAULT") (class "Default")
      (node (ref "LED3") (pin "A") (pinfunction "A_A") (pintype "passive"))
      (node (ref "R58") (pin "1") (pinfunction "1_1") (pintype "passive"))
    )
    (net (code "174") (name "Y2LO") (class "Default")
      (node (ref "R42") (pin "1") (pinfunction "1_1") (pintype "passive"))
      (node (ref "R58") (pin "2") (pinfunction "2_2") (pintype "passive"))
      (node (ref "U$2") (pin "LO") (pinfunction "LO_LO") (pintype "bidirectional"))
    )
    (net (code "175") (name "Y2RSA2") (class "Default")
      (node (ref "R40") (pin "1") (pinfunction "1_1") (pintype "passive"))
      (node (ref "U$2") (pin "RSA") (pinfunction "RSA1_RSA") (pintype "bidirectional"))
      (node (ref "U$2") (pin "RSA2") (pinfunction "RSA2_RSA2") (pintype "bidirectional"))
    )
    (net (code "176") (name "Y2RSB2") (class "Default")
      (node (ref "R39") (pin "1") (pinfunction "1_1") (pintype "passive"))
      (node (ref "U$2") (pin "RSB1") (pinfunction "RSB1_RSB1") (pintype "bidirectional"))
      (node (ref "U$2") (pin "RSB2") (pinfunction "RSB2_RSB2") (pintype "bidirectional"))
    )
    (net (code "177") (name "Y2VCCINT") (class "Default")
      (node (ref "C24") (pin "1") (pinfunction "1_1") (pintype "passive"))
      (node (ref "U$2") (pin "VCC") (pinfunction "VCC_VCC") (pintype "bidirectional"))
    )
    (net (code "178") (name "YFAULT") (class "Default")
      (node (ref "LED2") (pin "A") (pinfunction "A_A") (pintype "passive"))
      (node (ref "R57") (pin "1") (pinfunction "1_1") (pintype "passive"))
    )
    (net (code "179") (name "YLO") (class "Default")
      (node (ref "R33") (pin "1") (pinfunction "1_1") (pintype "passive"))
      (node (ref "R57") (pin "2") (pinfunction "2_2") (pintype "passive"))
      (node (ref "U$1") (pin "LO") (pinfunction "LO_LO") (pintype "bidirectional"))
    )
    (net (code "180") (name "YMODE0") (class "Default")
      (node (ref "R15") (pin "1") (pinfunction "1_1") (pintype "passive"))
      (node (ref "U$1") (pin "DMODE0") (pinfunction "DMODE0_DMODE0") (pintype "bidirectional"))
    )
    (net (code "181") (name "YMODE1") (class "Default")
      (node (ref "R16") (pin "1") (pinfunction "1_1") (pintype "passive"))
      (node (ref "SJ3") (pin "2") (pinfunction "2_2") (pintype "passive"))
      (node (ref "U$1") (pin "DMODE1") (pinfunction "DMODE1_DMODE1") (pintype "bidirectional"))
    )
    (net (code "182") (name "YMODE2") (class "Default")
      (node (ref "R29") (pin "1") (pinfunction "1_1") (pintype "passive"))
      (node (ref "SJ4") (pin "2") (pinfunction "2_2") (pintype "passive"))
      (node (ref "U$1") (pin "DMODE2") (pinfunction "DMODE2_DMODE2") (pintype "bidirectional"))
    )
    (net (code "183") (name "YOUT-A+") (class "Default")
      (node (ref "D5") (pin "C") (pinfunction "C_C") (pintype "passive"))
      (node (ref "J6") (pin "1") (pinfunction "1_1") (pintype "passive"))
      (node (ref "J6") (pin "2") (pinfunction "2_2") (pintype "passive"))
      (node (ref "U$1") (pin "OUTA+1") (pinfunction "OUTA+1_OUTA+1") (pintype "bidirectional"))
      (node (ref "U$1") (pin "OUTA+2") (pinfunction "OUTA+2_OUTA+2") (pintype "bidirectional"))
    )
    (net (code "184") (name "YOUT-A-") (class "Default")
      (node (ref "D5") (pin "A") (pinfunction "A_A") (pintype "passive"))
      (node (ref "J6") (pin "3") (pinfunction "3_3") (pintype "passive"))
      (node (ref "J6") (pin "4") (pinfunction "4_4") (pintype "passive"))
      (node (ref "U$1") (pin "OUTA-1") (pinfunction "OUTA-1_OUTA-1") (pintype "bidirectional"))
      (node (ref "U$1") (pin "OUTA-2") (pinfunction "OUTA-2_OUTA-2") (pintype "bidirectional"))
    )
    (net (code "185") (name "YOUT-B+") (class "Default")
      (node (ref "D6") (pin "A") (pinfunction "A_A") (pintype "passive"))
      (node (ref "J6") (pin "7") (pinfunction "7_7") (pintype "passive"))
      (node (ref "J6") (pin "8") (pinfunction "8_8") (pintype "passive"))
      (node (ref "U$1") (pin "OUTB+1") (pinfunction "OUTB+1_OUTB+1") (pintype "bidirectional"))
      (node (ref "U$1") (pin "OUTB+2") (pinfunction "OUTB+2_OUTB+2") (pintype "bidirectional"))
    )
    (net (code "186") (name "YOUT-B-") (class "Default")
      (node (ref "D6") (pin "C") (pinfunction "C_C") (pintype "passive"))
      (node (ref "J6") (pin "5") (pinfunction "5_5") (pintype "passive"))
      (node (ref "J6") (pin "6") (pinfunction "6_6") (pintype "passive"))
      (node (ref "U$1") (pin "OUTB-1") (pinfunction "OUTB-1_OUTB-1") (pintype "bidirectional"))
      (node (ref "U$1") (pin "OUTB-2") (pinfunction "OUTB-2_OUTB-2") (pintype "bidirectional"))
    )
    (net (code "187") (name "YVCCINT") (class "Default")
      (node (ref "C19") (pin "1") (pinfunction "1_1") (pintype "passive"))
      (node (ref "U$1") (pin "VCC") (pinfunction "VCC_VCC") (pintype "bidirectional"))
    )
    (net (code "188") (name "ZFAULT") (class "Default")
      (node (ref "LED4") (pin "A") (pinfunction "A_A") (pintype "passive"))
      (node (ref "R59") (pin "1") (pinfunction "1_1") (pintype "passive"))
    )
    (net (code "189") (name "ZLO") (class "Default")
      (node (ref "R51") (pin "1") (pinfunction "1_1") (pintype "passive"))
      (node (ref "R59") (pin "2") (pinfunction "2_2") (pintype "passive"))
      (node (ref "U$7") (pin "LO") (pinfunction "LO_LO") (pintype "bidirectional"))
    )
    (net (code "190") (name "ZMODE0") (class "Default")
      (node (ref "R36") (pin "1") (pinfunction "1_1") (pintype "passive"))
      (node (ref "U$2") (pin "DMODE0") (pinfunction "DMODE0_DMODE0") (pintype "bidirectional"))
    )
    (net (code "191") (name "ZMODE1") (class "Default")
      (node (ref "R37") (pin "1") (pinfunction "1_1") (pintype "passive"))
      (node (ref "SJ7") (pin "2") (pinfunction "2_2") (pintype "passive"))
      (node (ref "U$2") (pin "DMODE1") (pinfunction "DMODE1_DMODE1") (pintype "bidirectional"))
    )
    (net (code "192") (name "ZMODE2") (class "Default")
      (node (ref "R38") (pin "1") (pinfunction "1_1") (pintype "passive"))
      (node (ref "SJ8") (pin "2") (pinfunction "2_2") (pintype "passive"))
      (node (ref "U$2") (pin "DMODE2") (pinfunction "DMODE2_DMODE2") (pintype "bidirectional"))
    )
    (net (code "193") (name "ZOUT-A+") (class "Default")
      (node (ref "D7") (pin "C") (pinfunction "C_C") (pintype "passive"))
      (node (ref "J8") (pin "1") (pinfunction "1_1") (pintype "passive"))
      (node (ref "J8") (pin "2") (pinfunction "2_2") (pintype "passive"))
      (node (ref "U$2") (pin "OUTA+1") (pinfunction "OUTA+1_OUTA+1") (pintype "bidirectional"))
      (node (ref "U$2") (pin "OUTA+2") (pinfunction "OUTA+2_OUTA+2") (pintype "bidirectional"))
    )
    (net (code "194") (name "ZOUT-A-") (class "Default")
      (node (ref "D7") (pin "A") (pinfunction "A_A") (pintype "passive"))
      (node (ref "J8") (pin "3") (pinfunction "3_3") (pintype "passive"))
      (node (ref "J8") (pin "4") (pinfunction "4_4") (pintype "passive"))
      (node (ref "U$2") (pin "OUTA-1") (pinfunction "OUTA-1_OUTA-1") (pintype "bidirectional"))
      (node (ref "U$2") (pin "OUTA-2") (pinfunction "OUTA-2_OUTA-2") (pintype "bidirectional"))
    )
    (net (code "195") (name "ZOUT-B+") (class "Default")
      (node (ref "D8") (pin "A") (pinfunction "A_A") (pintype "passive"))
      (node (ref "J8") (pin "7") (pinfunction "7_7") (pintype "passive"))
      (node (ref "J8") (pin "8") (pinfunction "8_8") (pintype "passive"))
      (node (ref "U$2") (pin "OUTB+1") (pinfunction "OUTB+1_OUTB+1") (pintype "bidirectional"))
      (node (ref "U$2") (pin "OUTB+2") (pinfunction "OUTB+2_OUTB+2") (pintype "bidirectional"))
    )
    (net (code "196") (name "ZOUT-B-") (class "Default")
      (node (ref "D8") (pin "C") (pinfunction "C_C") (pintype "passive"))
      (node (ref "J8") (pin "5") (pinfunction "5_5") (pintype "passive"))
      (node (ref "J8") (pin "6") (pinfunction "6_6") (pintype "passive"))
      (node (ref "U$2") (pin "OUTB-1") (pinfunction "OUTB-1_OUTB-1") (pintype "bidirectional"))
      (node (ref "U$2") (pin "OUTB-2") (pinfunction "OUTB-2_OUTB-2") (pintype "bidirectional"))
    )
    (net (code "197") (name "ZRSA3") (class "Default")
      (node (ref "R49") (pin "1") (pinfunction "1_1") (pintype "passive"))
      (node (ref "U$7") (pin "RSA") (pinfunction "RSA1_RSA") (pintype "bidirectional"))
      (node (ref "U$7") (pin "RSA2") (pinfunction "RSA2_RSA2") (pintype "bidirectional"))
    )
    (net (code "198") (name "ZRSB3") (class "Default")
      (node (ref "R48") (pin "1") (pinfunction "1_1") (pintype "passive"))
      (node (ref "U$7") (pin "RSB1") (pinfunction "RSB1_RSB1") (pintype "bidirectional"))
      (node (ref "U$7") (pin "RSB2") (pinfunction "RSB2_RSB2") (pintype "bidirectional"))
    )
    (net (code "199") (name "ZVCCINT") (class "Default")
      (node (ref "C34") (pin "1") (pinfunction "1_1") (pintype "passive"))
      (node (ref "U$7") (pin "VCC") (pinfunction "VCC_VCC") (pintype "bidirectional"))
    )
    (net (code "200") (name "_E-ENDSTOP-C1") (class "Default")
      (node (ref "D20") (pin "C") (pinfunction "C_C") (pintype "passive"))
      (node (ref "J7") (pin "9") (pinfunction "9_9") (pintype "passive"))
    )
    (net (code "201") (name "_X-ENDSTOP-C1") (class "Default")
      (node (ref "D16") (pin "C") (pinfunction "C_C") (pintype "passive"))
      (node (ref "Z-CONN1") (pin "9") (pinfunction "9_9") (pintype "passive"))
    )
    (net (code "202") (name "_Y-ENDSTOP-C1") (class "Default")
      (node (ref "D17") (pin "C") (pinfunction "C_C") (pintype "passive"))
      (node (ref "J6") (pin "9") (pinfunction "9_9") (pintype "passive"))
    )
    (net (code "203") (name "_Z-ENDSTOP-C1") (class "Default")
      (node (ref "D19") (pin "C") (pinfunction "C_C") (pintype "passive"))
      (node (ref "J8") (pin "9") (pinfunction "9_9") (pintype "passive"))
    )
    (net (code "204") (name "unconnected-(IC3-(ICP1)PD4-Pad47)") (class "Default")
      (node (ref "IC3") (pin "47") (pinfunction "(ICP1)PD4_47") (pintype "bidirectional"))
    )
    (net (code "205") (name "unconnected-(IC3-(T1)PD6-Pad49)") (class "Default")
      (node (ref "IC3") (pin "49") (pinfunction "(T1)PD6_49") (pintype "bidirectional"))
    )
    (net (code "206") (name "unconnected-(IC3-(TOSC1)PG4-Pad29)") (class "Default")
      (node (ref "IC3") (pin "29") (pinfunction "(TOSC1)PG4_29") (pintype "bidirectional"))
    )
    (net (code "207") (name "unconnected-(IC3-(TOSC2)PG3-Pad28)") (class "Default")
      (node (ref "IC3") (pin "28") (pinfunction "(TOSC2)PG3_28") (pintype "bidirectional"))
    )
    (net (code "208") (name "unconnected-(IC3-(XCK0{slash}AIN0)PE2-Pad4)") (class "Default")
      (node (ref "IC3") (pin "4") (pinfunction "(XCK0/AIN0)PE2_4") (pintype "bidirectional"))
    )
    (net (code "209") (name "unconnected-(IC3-(XCK1)PD5-Pad48)") (class "Default")
      (node (ref "IC3") (pin "48") (pinfunction "(XCK1)PD5_48") (pintype "bidirectional"))
    )
    (net (code "210") (name "unconnected-(IC3-PH2(XCK2)-Pad14)") (class "Default")
      (node (ref "IC3") (pin "14") (pinfunction "PH2(XCK2)_14") (pintype "bidirectional"))
    )
    (net (code "211") (name "unconnected-(IC3-PH7(T4)-Pad27)") (class "Default")
      (node (ref "IC3") (pin "27") (pinfunction "PH7(T4)_27") (pintype "bidirectional"))
    )
    (net (code "212") (name "unconnected-(IC3-PJ2(XCK3{slash}PCINT11)-Pad65)") (class "Default")
      (node (ref "IC3") (pin "65") (pinfunction "PJ2(XCK3/PCINT11)_65") (pintype "bidirectional"))
    )
    (net (code "213") (name "unconnected-(IC3-PJ3(PCINT12)-Pad66)") (class "Default")
      (node (ref "IC3") (pin "66") (pinfunction "PJ3(PCINT12)_66") (pintype "bidirectional"))
    )
    (net (code "214") (name "unconnected-(IC3-PJ4(PCINT13)-Pad67)") (class "Default")
      (node (ref "IC3") (pin "67") (pinfunction "PJ4(PCINT13)_67") (pintype "bidirectional"))
    )
    (net (code "215") (name "unconnected-(IC3-PJ5(PCINT14)-Pad68)") (class "Default")
      (node (ref "IC3") (pin "68") (pinfunction "PJ5(PCINT14)_68") (pintype "bidirectional"))
    )
    (net (code "216") (name "unconnected-(IC3-PJ6(PCINT15)-Pad69)") (class "Default")
      (node (ref "IC3") (pin "69") (pinfunction "PJ6(PCINT15)_69") (pintype "bidirectional"))
    )
    (net (code "217") (name "unconnected-(IC3-PJ7-Pad79)") (class "Default")
      (node (ref "IC3") (pin "79") (pinfunction "PJ7_79") (pintype "bidirectional"))
    )
    (net (code "218") (name "unconnected-(IC5A-OUT-Pad1)") (class "Default")
      (node (ref "IC5") (pin "1") (pinfunction "OUT_1") (pintype "output"))
    )
    (net (code "219") (name "unconnected-(U$1-PadNC1)") (class "Default")
      (node (ref "U$1") (pin "NC1") (pinfunction "NC1_NC1") (pintype "bidirectional"))
    )
    (net (code "220") (name "unconnected-(U$1-PadNC2)") (class "Default")
      (node (ref "U$1") (pin "NC2") (pinfunction "NC2_NC2") (pintype "bidirectional"))
    )
    (net (code "221") (name "unconnected-(U$1-PadNC3)") (class "Default")
      (node (ref "U$1") (pin "NC3") (pinfunction "NC3_NC3") (pintype "bidirectional"))
    )
    (net (code "222") (name "unconnected-(U$1-PadNC4)") (class "Default")
      (node (ref "U$1") (pin "NC4") (pinfunction "NC4_NC4") (pintype "bidirectional"))
    )
    (net (code "223") (name "unconnected-(U$1-PadNC5)") (class "Default")
      (node (ref "U$1") (pin "NC5") (pinfunction "NC5_NC5") (pintype "bidirectional"))
    )
    (net (code "224") (name "unconnected-(U$1-PadNC6)") (class "Default")
      (node (ref "U$1") (pin "NC6") (pinfunction "NC6_NC6") (pintype "bidirectional"))
    )
    (net (code "225") (name "unconnected-(U$1-PadNC7)") (class "Default")
      (node (ref "U$1") (pin "NC7") (pinfunction "NC7_NC7") (pintype "bidirectional"))
    )
    (net (code "226") (name "unconnected-(U$1-PadNC8)") (class "Default")
      (node (ref "U$1") (pin "NC8") (pinfunction "NC8_NC8") (pintype "bidirectional"))
    )
    (net (code "227") (name "unconnected-(U$1-PadNC9)") (class "Default")
      (node (ref "U$1") (pin "NC9") (pinfunction "NC9_NC9") (pintype "bidirectional"))
    )
    (net (code "228") (name "unconnected-(U$1-PadNC10)") (class "Default")
      (node (ref "U$1") (pin "NC10") (pinfunction "NC10_NC10") (pintype "bidirectional"))
    )
    (net (code "229") (name "unconnected-(U$1-PadNC11)") (class "Default")
      (node (ref "U$1") (pin "NC11") (pinfunction "NC11_NC11") (pintype "bidirectional"))
    )
    (net (code "230") (name "unconnected-(U$1-PadNC12)") (class "Default")
      (node (ref "U$1") (pin "NC12") (pinfunction "NC12_NC12") (pintype "bidirectional"))
    )
    (net (code "231") (name "unconnected-(U$1-PadNC13)") (class "Default")
      (node (ref "U$1") (pin "NC13") (pinfunction "NC13_NC13") (pintype "bidirectional"))
    )
    (net (code "232") (name "unconnected-(U$1-PadNC14)") (class "Default")
      (node (ref "U$1") (pin "NC14") (pinfunction "NC14_NC14") (pintype "bidirectional"))
    )
    (net (code "233") (name "unconnected-(U$1-PadNC15)") (class "Default")
      (node (ref "U$1") (pin "NC15") (pinfunction "NC15_NC15") (pintype "bidirectional"))
    )
    (net (code "234") (name "unconnected-(U$1-PadNC16)") (class "Default")
      (node (ref "U$1") (pin "NC16") (pinfunction "NC16_NC16") (pintype "bidirectional"))
    )
    (net (code "235") (name "unconnected-(U$1-PadRESET)") (class "Default")
      (node (ref "U$1") (pin "RESET") (pinfunction "RESET_RESET") (pintype "bidirectional"))
    )
    (net (code "236") (name "unconnected-(U$2-PadNC1)") (class "Default")
      (node (ref "U$2") (pin "NC1") (pinfunction "NC1_NC1") (pintype "bidirectional"))
    )
    (net (code "237") (name "unconnected-(U$2-PadNC2)") (class "Default")
      (node (ref "U$2") (pin "NC2") (pinfunction "NC2_NC2") (pintype "bidirectional"))
    )
    (net (code "238") (name "unconnected-(U$2-PadNC3)") (class "Default")
      (node (ref "U$2") (pin "NC3") (pinfunction "NC3_NC3") (pintype "bidirectional"))
    )
    (net (code "239") (name "unconnected-(U$2-PadNC4)") (class "Default")
      (node (ref "U$2") (pin "NC4") (pinfunction "NC4_NC4") (pintype "bidirectional"))
    )
    (net (code "240") (name "unconnected-(U$2-PadNC5)") (class "Default")
      (node (ref "U$2") (pin "NC5") (pinfunction "NC5_NC5") (pintype "bidirectional"))
    )
    (net (code "241") (name "unconnected-(U$2-PadNC6)") (class "Default")
      (node (ref "U$2") (pin "NC6") (pinfunction "NC6_NC6") (pintype "bidirectional"))
    )
    (net (code "242") (name "unconnected-(U$2-PadNC7)") (class "Default")
      (node (ref "U$2") (pin "NC7") (pinfunction "NC7_NC7") (pintype "bidirectional"))
    )
    (net (code "243") (name "unconnected-(U$2-PadNC8)") (class "Default")
      (node (ref "U$2") (pin "NC8") (pinfunction "NC8_NC8") (pintype "bidirectional"))
    )
    (net (code "244") (name "unconnected-(U$2-PadNC9)") (class "Default")
      (node (ref "U$2") (pin "NC9") (pinfunction "NC9_NC9") (pintype "bidirectional"))
    )
    (net (code "245") (name "unconnected-(U$2-PadNC10)") (class "Default")
      (node (ref "U$2") (pin "NC10") (pinfunction "NC10_NC10") (pintype "bidirectional"))
    )
    (net (code "246") (name "unconnected-(U$2-PadNC11)") (class "Default")
      (node (ref "U$2") (pin "NC11") (pinfunction "NC11_NC11") (pintype "bidirectional"))
    )
    (net (code "247") (name "unconnected-(U$2-PadNC12)") (class "Default")
      (node (ref "U$2") (pin "NC12") (pinfunction "NC12_NC12") (pintype "bidirectional"))
    )
    (net (code "248") (name "unconnected-(U$2-PadNC13)") (class "Default")
      (node (ref "U$2") (pin "NC13") (pinfunction "NC13_NC13") (pintype "bidirectional"))
    )
    (net (code "249") (name "unconnected-(U$2-PadNC14)") (class "Default")
      (node (ref "U$2") (pin "NC14") (pinfunction "NC14_NC14") (pintype "bidirectional"))
    )
    (net (code "250") (name "unconnected-(U$2-PadNC15)") (class "Default")
      (node (ref "U$2") (pin "NC15") (pinfunction "NC15_NC15") (pintype "bidirectional"))
    )
    (net (code "251") (name "unconnected-(U$2-PadNC16)") (class "Default")
      (node (ref "U$2") (pin "NC16") (pinfunction "NC16_NC16") (pintype "bidirectional"))
    )
    (net (code "252") (name "unconnected-(U$2-PadRESET)") (class "Default")
      (node (ref "U$2") (pin "RESET") (pinfunction "RESET_RESET") (pintype "bidirectional"))
    )
    (net (code "253") (name "unconnected-(U$7-PadNC1)") (class "Default")
      (node (ref "U$7") (pin "NC1") (pinfunction "NC1_NC1") (pintype "bidirectional"))
    )
    (net (code "254") (name "unconnected-(U$7-PadNC2)") (class "Default")
      (node (ref "U$7") (pin "NC2") (pinfunction "NC2_NC2") (pintype "bidirectional"))
    )
    (net (code "255") (name "unconnected-(U$7-PadNC3)") (class "Default")
      (node (ref "U$7") (pin "NC3") (pinfunction "NC3_NC3") (pintype "bidirectional"))
    )
    (net (code "256") (name "unconnected-(U$7-PadNC4)") (class "Default")
      (node (ref "U$7") (pin "NC4") (pinfunction "NC4_NC4") (pintype "bidirectional"))
    )
    (net (code "257") (name "unconnected-(U$7-PadNC5)") (class "Default")
      (node (ref "U$7") (pin "NC5") (pinfunction "NC5_NC5") (pintype "bidirectional"))
    )
    (net (code "258") (name "unconnected-(U$7-PadNC6)") (class "Default")
      (node (ref "U$7") (pin "NC6") (pinfunction "NC6_NC6") (pintype "bidirectional"))
    )
    (net (code "259") (name "unconnected-(U$7-PadNC7)") (class "Default")
      (node (ref "U$7") (pin "NC7") (pinfunction "NC7_NC7") (pintype "bidirectional"))
    )
    (net (code "260") (name "unconnected-(U$7-PadNC8)") (class "Default")
      (node (ref "U$7") (pin "NC8") (pinfunction "NC8_NC8") (pintype "bidirectional"))
    )
    (net (code "261") (name "unconnected-(U$7-PadNC9)") (class "Default")
      (node (ref "U$7") (pin "NC9") (pinfunction "NC9_NC9") (pintype "bidirectional"))
    )
    (net (code "262") (name "unconnected-(U$7-PadNC10)") (class "Default")
      (node (ref "U$7") (pin "NC10") (pinfunction "NC10_NC10") (pintype "bidirectional"))
    )
    (net (code "263") (name "unconnected-(U$7-PadNC11)") (class "Default")
      (node (ref "U$7") (pin "NC11") (pinfunction "NC11_NC11") (pintype "bidirectional"))
    )
    (net (code "264") (name "unconnected-(U$7-PadNC12)") (class "Default")
      (node (ref "U$7") (pin "NC12") (pinfunction "NC12_NC12") (pintype "bidirectional"))
    )
    (net (code "265") (name "unconnected-(U$7-PadNC13)") (class "Default")
      (node (ref "U$7") (pin "NC13") (pinfunction "NC13_NC13") (pintype "bidirectional"))
    )
    (net (code "266") (name "unconnected-(U$7-PadNC14)") (class "Default")
      (node (ref "U$7") (pin "NC14") (pinfunction "NC14_NC14") (pintype "bidirectional"))
    )
    (net (code "267") (name "unconnected-(U$7-PadNC15)") (class "Default")
      (node (ref "U$7") (pin "NC15") (pinfunction "NC15_NC15") (pintype "bidirectional"))
    )
    (net (code "268") (name "unconnected-(U$7-PadNC16)") (class "Default")
      (node (ref "U$7") (pin "NC16") (pinfunction "NC16_NC16") (pintype "bidirectional"))
    )
    (net (code "269") (name "unconnected-(U$7-PadRESET)") (class "Default")
      (node (ref "U$7") (pin "RESET") (pinfunction "RESET_RESET") (pintype "bidirectional"))
    )
    (net (code "270") (name "unconnected-(U$17-PadNC1)") (class "Default")
      (node (ref "U$17") (pin "NC1") (pinfunction "NC1_NC1") (pintype "bidirectional"))
    )
    (net (code "271") (name "unconnected-(U$17-PadNC2)") (class "Default")
      (node (ref "U$17") (pin "NC2") (pinfunction "NC2_NC2") (pintype "bidirectional"))
    )
    (net (code "272") (name "unconnected-(U$17-PadNC3)") (class "Default")
      (node (ref "U$17") (pin "NC3") (pinfunction "NC3_NC3") (pintype "bidirectional"))
    )
    (net (code "273") (name "unconnected-(U$17-PadNC4)") (class "Default")
      (node (ref "U$17") (pin "NC4") (pinfunction "NC4_NC4") (pintype "bidirectional"))
    )
    (net (code "274") (name "unconnected-(U$17-PadNC5)") (class "Default")
      (node (ref "U$17") (pin "NC5") (pinfunction "NC5_NC5") (pintype "bidirectional"))
    )
    (net (code "275") (name "unconnected-(U$17-PadNC6)") (class "Default")
      (node (ref "U$17") (pin "NC6") (pinfunction "NC6_NC6") (pintype "bidirectional"))
    )
    (net (code "276") (name "unconnected-(U$17-PadNC7)") (class "Default")
      (node (ref "U$17") (pin "NC7") (pinfunction "NC7_NC7") (pintype "bidirectional"))
    )
    (net (code "277") (name "unconnected-(U$17-PadNC8)") (class "Default")
      (node (ref "U$17") (pin "NC8") (pinfunction "NC8_NC8") (pintype "bidirectional"))
    )
    (net (code "278") (name "unconnected-(U$17-PadNC9)") (class "Default")
      (node (ref "U$17") (pin "NC9") (pinfunction "NC9_NC9") (pintype "bidirectional"))
    )
    (net (code "279") (name "unconnected-(U$17-PadNC10)") (class "Default")
      (node (ref "U$17") (pin "NC10") (pinfunction "NC10_NC10") (pintype "bidirectional"))
    )
    (net (code "280") (name "unconnected-(U$17-PadNC11)") (class "Default")
      (node (ref "U$17") (pin "NC11") (pinfunction "NC11_NC11") (pintype "bidirectional"))
    )
    (net (code "281") (name "unconnected-(U$17-PadNC12)") (class "Default")
      (node (ref "U$17") (pin "NC12") (pinfunction "NC12_NC12") (pintype "bidirectional"))
    )
    (net (code "282") (name "unconnected-(U$17-PadNC13)") (class "Default")
      (node (ref "U$17") (pin "NC13") (pinfunction "NC13_NC13") (pintype "bidirectional"))
    )
    (net (code "283") (name "unconnected-(U$17-PadNC14)") (class "Default")
      (node (ref "U$17") (pin "NC14") (pinfunction "NC14_NC14") (pintype "bidirectional"))
    )
    (net (code "284") (name "unconnected-(U$17-PadNC15)") (class "Default")
      (node (ref "U$17") (pin "NC15") (pinfunction "NC15_NC15") (pintype "bidirectional"))
    )
    (net (code "285") (name "unconnected-(U$17-PadNC16)") (class "Default")
      (node (ref "U$17") (pin "NC16") (pinfunction "NC16_NC16") (pintype "bidirectional"))
    )
    (net (code "286") (name "unconnected-(U$17-PadRESET)") (class "Default")
      (node (ref "U$17") (pin "RESET") (pinfunction "RESET_RESET") (pintype "bidirectional"))
    )
    (net (code "287") (name "unconnected-(U2-NC-Pad1)") (class "Default")
      (node (ref "U2") (pin "1") (pinfunction "NC_1") (pintype "bidirectional"))
    )
    (net (code "288") (name "unconnected-(U2-RSV-Pad8)") (class "Default")
      (node (ref "U2") (pin "8") (pinfunction "RSV_8") (pintype "bidirectional"))
    )
    (net (code "289") (name "unconnected-(U2-SHIELD-PadCDNC1)") (class "Default")
      (node (ref "U2") (pin "CDNC1") (pinfunction "SHIELD_CDNC1") (pintype "bidirectional"))
    )
    (net (code "290") (name "unconnected-(U2-SHIELD-PadCDNC2)") (class "Default")
      (node (ref "U2") (pin "CDNC2") (pinfunction "SHIELD_CDNC2") (pintype "bidirectional"))
    )
    (net (code "291") (name "unconnected-(U6-DCD-Pad10)") (class "Default")
      (node (ref "U6") (pin "10") (pinfunction "DCD_10") (pintype "input"))
    )
    (net (code "292") (name "unconnected-(U6-DSR-Pad9)") (class "Default")
      (node (ref "U6") (pin "9") (pinfunction "DSR_9") (pintype "input"))
    )
    (net (code "293") (name "unconnected-(U6-OSCI-Pad27)") (class "Default")
      (node (ref "U6") (pin "27") (pinfunction "OSCI_27") (pintype "input"))
    )
    (net (code "294") (name "unconnected-(U6-OSCO-Pad28)") (class "Default")
      (node (ref "U6") (pin "28") (pinfunction "OSCO_28") (pintype "output"))
    )
    (net (code "295") (name "unconnected-(U6-PWREN-Pad14)") (class "Default")
      (node (ref "U6") (pin "14") (pinfunction "PWREN_14") (pintype "input"))
    )
    (net (code "296") (name "unconnected-(U6-RESET-Pad19)") (class "Default")
      (node (ref "U6") (pin "19") (pinfunction "RESET_19") (pintype "input"))
    )
    (net (code "297") (name "unconnected-(U6-RI-Pad6)") (class "Default")
      (node (ref "U6") (pin "6") (pinfunction "RI_6") (pintype "input"))
    )
    (net (code "298") (name "unconnected-(U6-SLEEP-Pad12)") (class "Default")
      (node (ref "U6") (pin "12") (pinfunction "SLEEP_12") (pintype "input"))
    )
    (net (code "299") (name "unconnected-(U6-TXDEN-Pad13)") (class "Default")
      (node (ref "U6") (pin "13") (pinfunction "TXDEN_13") (pintype "input"))
    )
  )
)
